# io-board-b-b.net
KiCad netlist of a schematic drawn in EAGLE
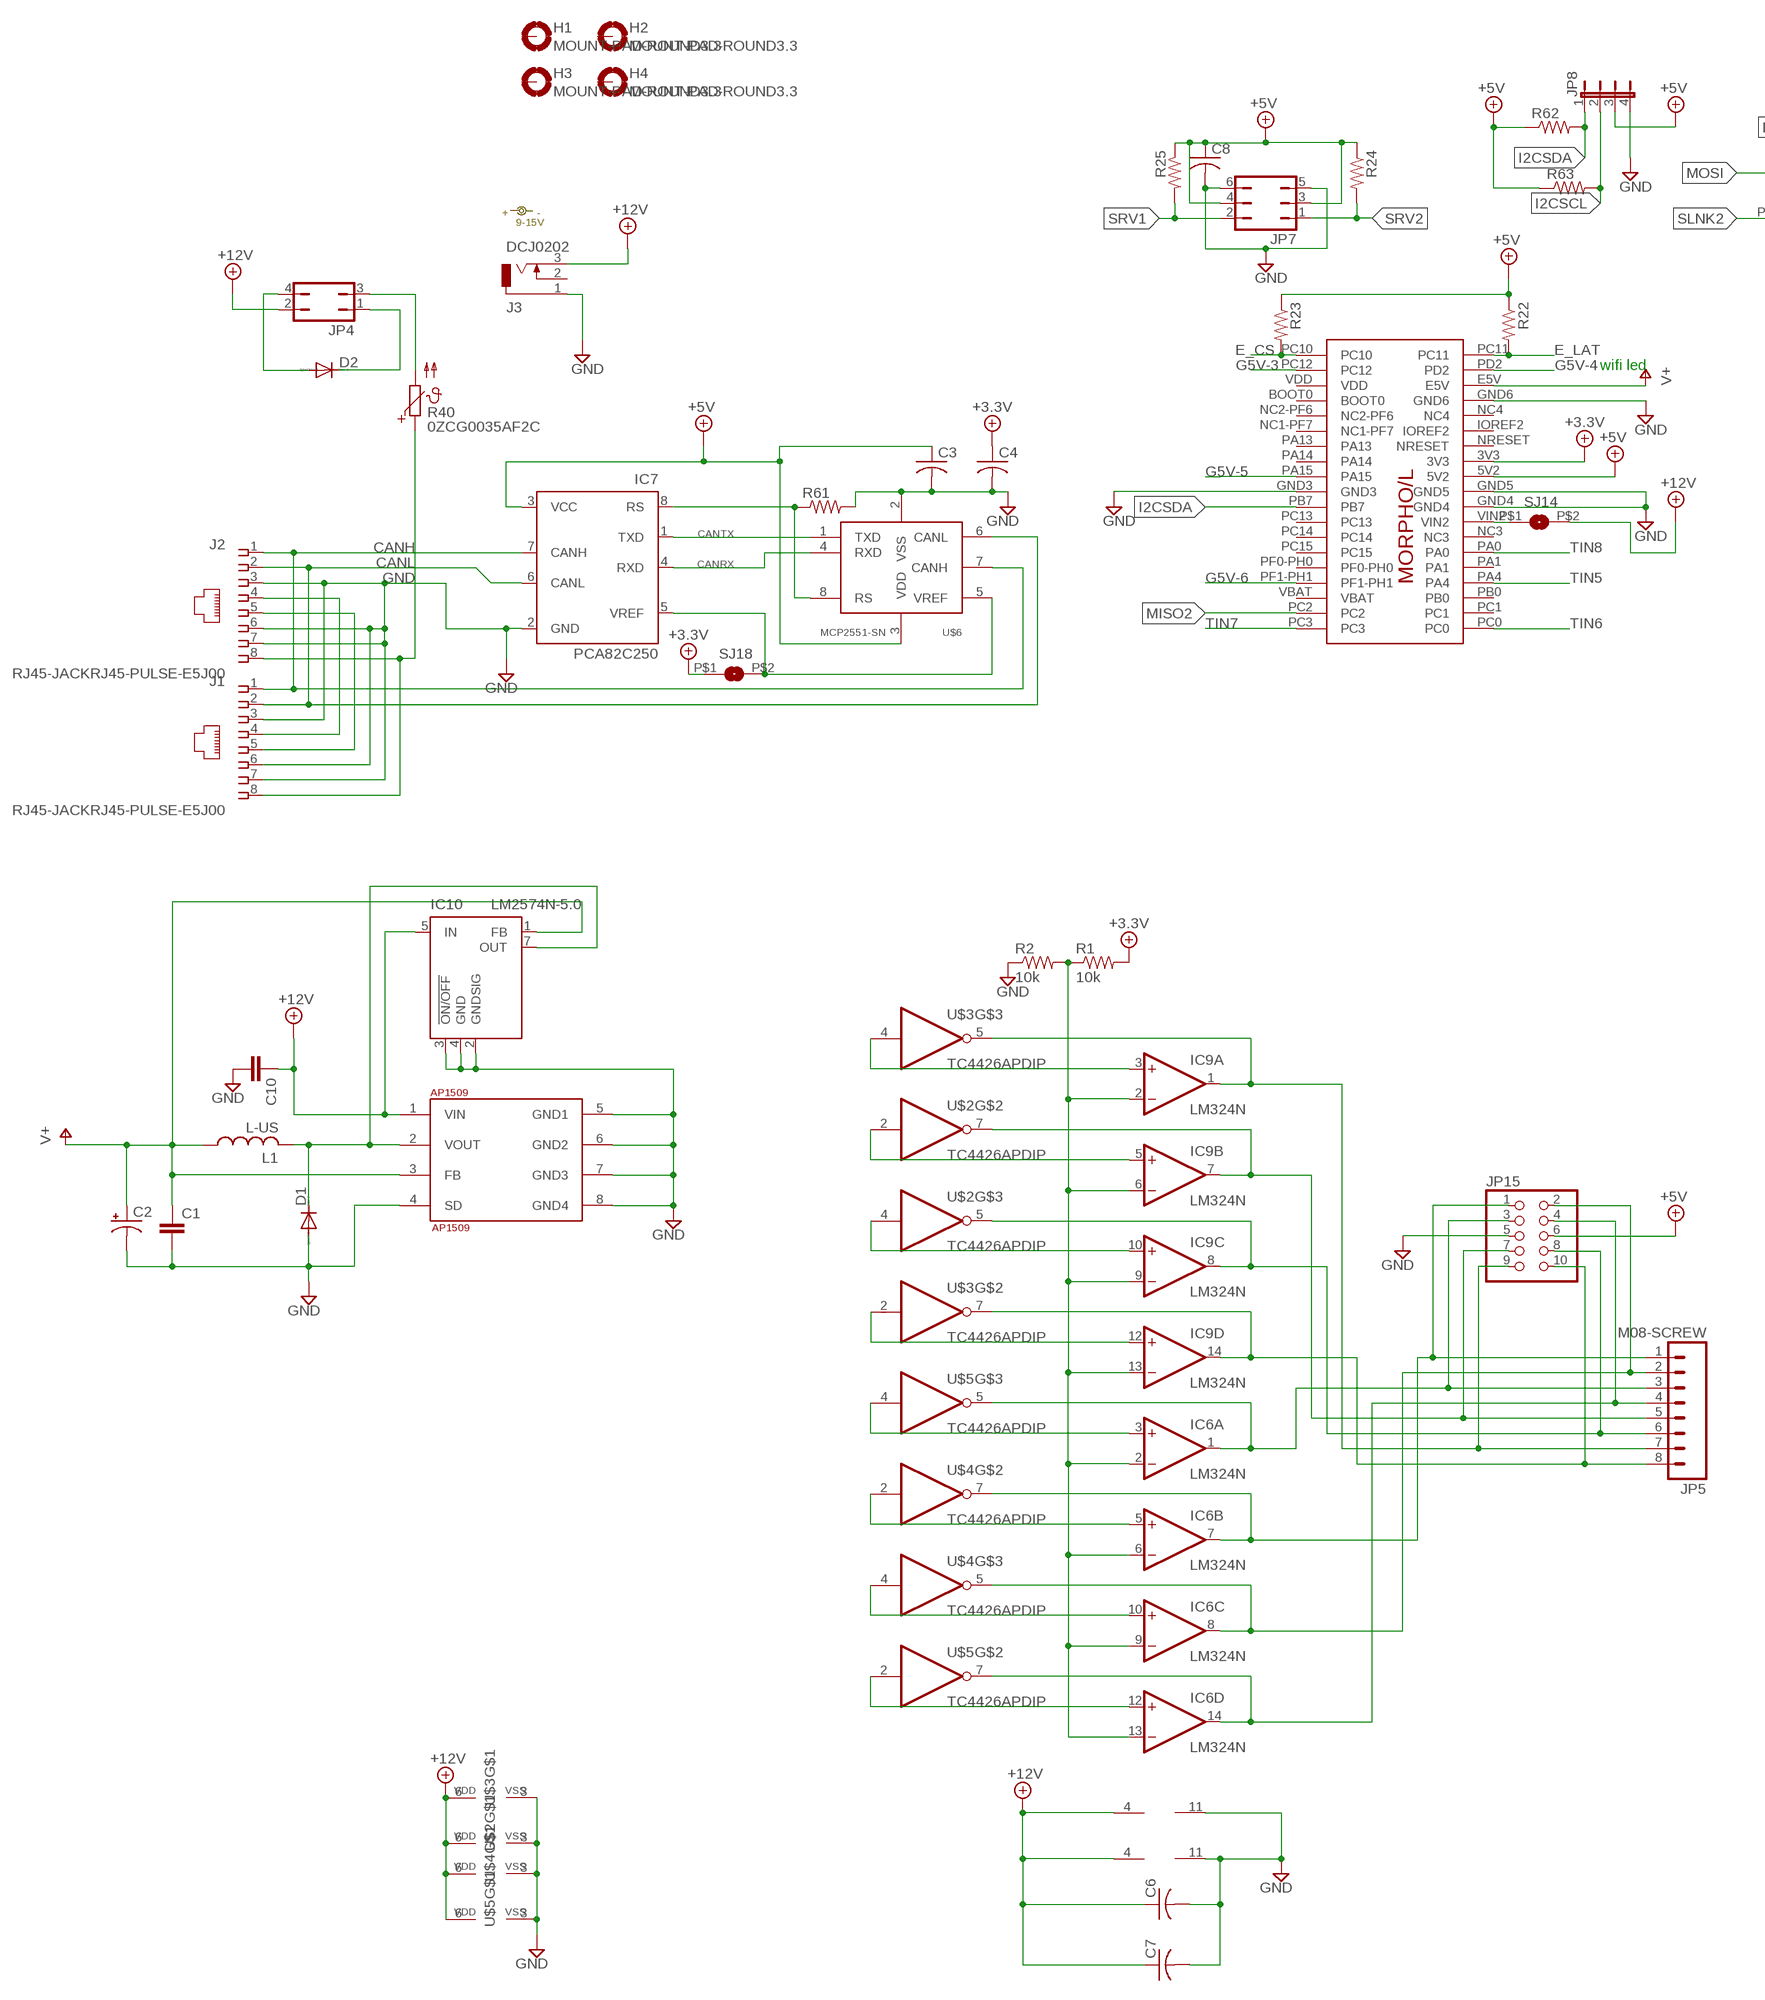
[diagram p0: schematic, sheet 1, part 1 of 2]
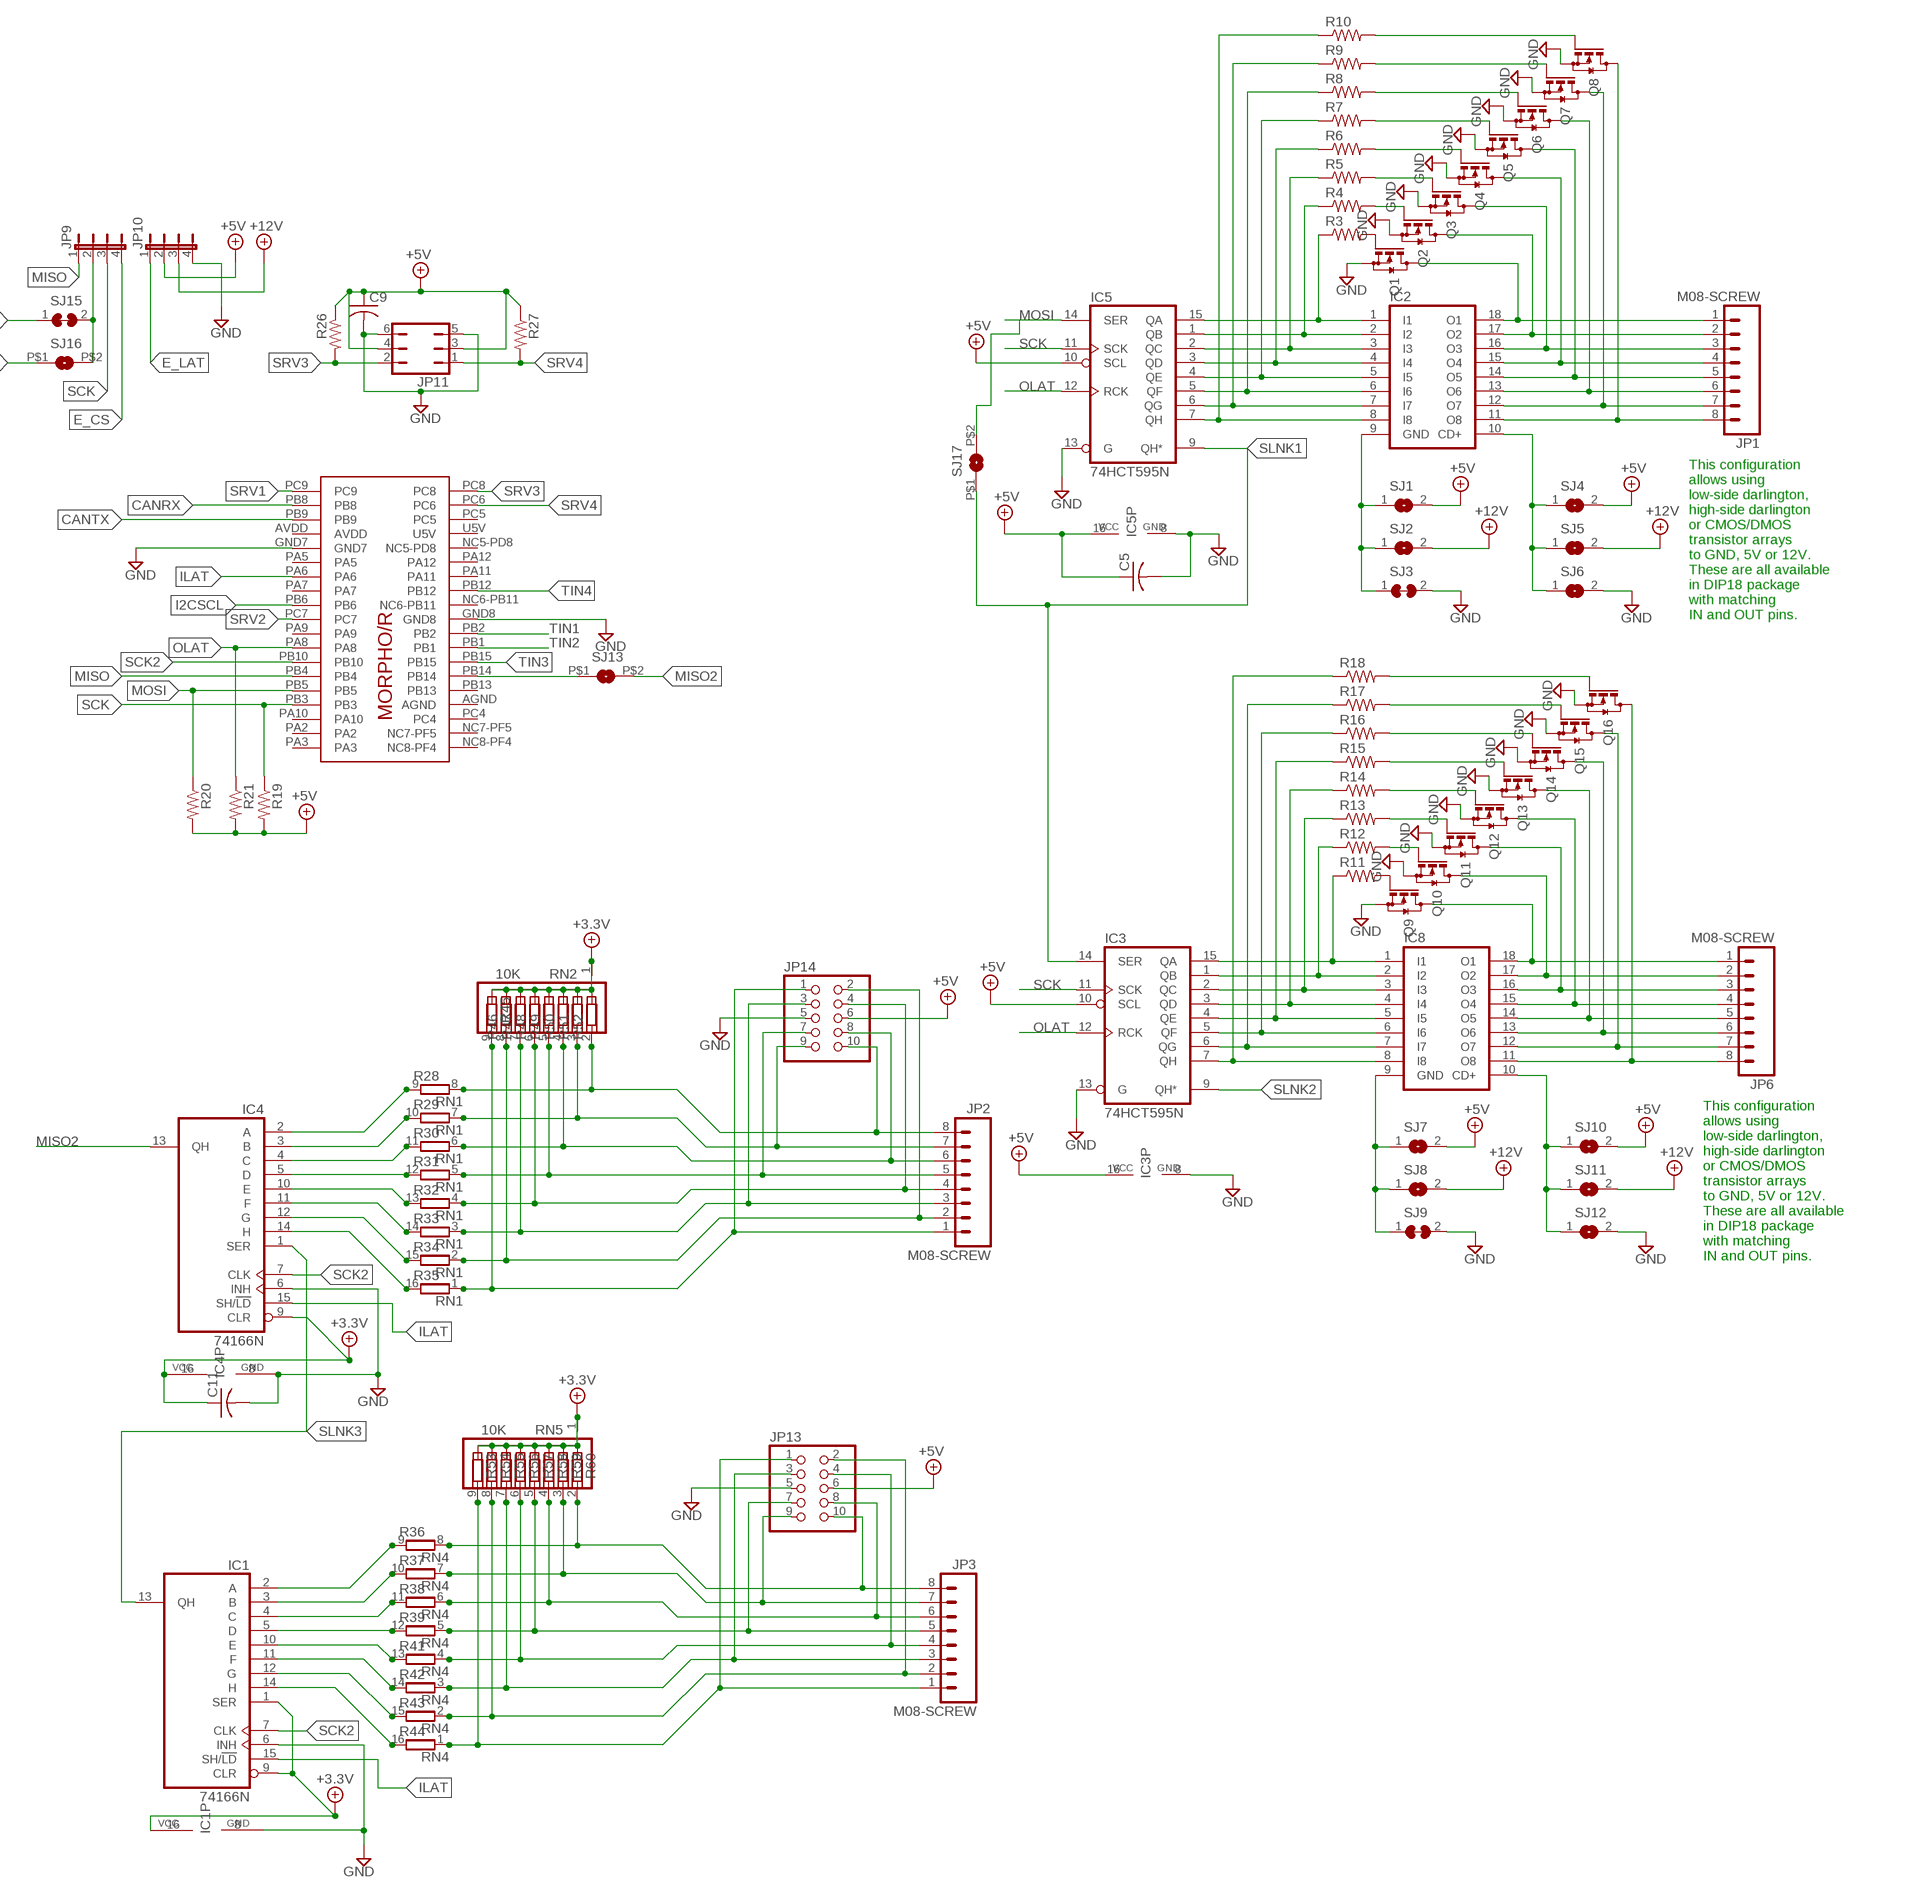
[diagram p1: schematic, sheet 1, part 2 of 2]

(export (version "E")
  (design (tool "Eeschema 10.0.6"))
  (components
    (comp (ref "+12V")
      (value "9-15V")
      (footprint "eagle-import:POWER_USAGE")
      (libsource (lib "eagle-import") (part "DOC-POWER_LABEL"))
    )
    (comp (ref "AP1509")
      (value "AP1509")
      (footprint "eagle-import:SO-08")
      (libsource (lib "eagle-import") (part "AP1509"))
    )
    (comp (ref "C1")
      (value "C-EUC1206")
      (footprint "eagle-import:C1206")
      (libsource (lib "eagle-import") (part "C-EUC1206"))
    )
    (comp (ref "C2")
      (value "CPOL-USE2.5-5")
      (footprint "eagle-import:E2,5-5")
      (libsource (lib "eagle-import") (part "CPOL-USE2.5-5"))
    )
    (comp (ref "C3")
      (value "C-USC0805")
      (footprint "eagle-import:C0805")
      (libsource (lib "eagle-import") (part "C-USC0805"))
    )
    (comp (ref "C4")
      (value "C-USC0805")
      (footprint "eagle-import:C0805")
      (libsource (lib "eagle-import") (part "C-USC0805"))
    )
    (comp (ref "C5")
      (value "C-USC0805")
      (footprint "eagle-import:C0805")
      (libsource (lib "eagle-import") (part "C-USC0805"))
    )
    (comp (ref "C6")
      (value "C-USC1206")
      (footprint "eagle-import:C1206")
      (libsource (lib "eagle-import") (part "C-USC1206"))
    )
    (comp (ref "C7")
      (value "C-USC1206")
      (footprint "eagle-import:C1206")
      (libsource (lib "eagle-import") (part "C-USC1206"))
    )
    (comp (ref "C8")
      (value "C-USC1206")
      (footprint "eagle-import:C1206")
      (libsource (lib "eagle-import") (part "C-USC1206"))
    )
    (comp (ref "C9")
      (value "C-USC1206")
      (footprint "eagle-import:C1206")
      (libsource (lib "eagle-import") (part "C-USC1206"))
    )
    (comp (ref "C10")
      (value "C-EUC1206")
      (footprint "eagle-import:C1206")
      (libsource (lib "eagle-import") (part "C-EUC1206"))
    )
    (comp (ref "C11")
      (value "C-USC0805")
      (footprint "eagle-import:C0805")
      (libsource (lib "eagle-import") (part "C-USC0805"))
    )
    (comp (ref "D1")
      (value "DIODE-DO41-7.6")
      (footprint "eagle-import:DO41-7.6")
      (libsource (lib "eagle-import") (part "DIODE-DO41-7.6"))
    )
    (comp (ref "D2")
      (value "DIODE-DO41-7.6")
      (footprint "eagle-import:DO41-7.6")
      (libsource (lib "eagle-import") (part "DIODE-DO41-7.6"))
    )
    (comp (ref "H1")
      (value "MOUNT-PAD-ROUND3.3")
      (footprint "eagle-import:3,3-PAD")
      (libsource (lib "eagle-import") (part "MOUNT-PAD-ROUND3.3"))
    )
    (comp (ref "H2")
      (value "MOUNT-PAD-ROUND3.3")
      (footprint "eagle-import:3,3-PAD")
      (libsource (lib "eagle-import") (part "MOUNT-PAD-ROUND3.3"))
    )
    (comp (ref "H3")
      (value "MOUNT-PAD-ROUND3.3")
      (footprint "eagle-import:3,3-PAD")
      (libsource (lib "eagle-import") (part "MOUNT-PAD-ROUND3.3"))
    )
    (comp (ref "H4")
      (value "MOUNT-PAD-ROUND3.3")
      (footprint "eagle-import:3,3-PAD")
      (libsource (lib "eagle-import") (part "MOUNT-PAD-ROUND3.3"))
    )
    (comp (ref "IC1")
      (value "74166N")
      (footprint "eagle-import:DIL16")
      (libsource (lib "eagle-import") (part "74166N"))
    )
    (comp (ref "IC2")
      (value "ULN2803A")
      (footprint "eagle-import:DIL18-THIN")
      (libsource (lib "eagle-import") (part "ULN2803A"))
    )
    (comp (ref "IC3")
      (value "74HCT595N")
      (footprint "eagle-import:DIL16")
      (libsource (lib "eagle-import") (part "74595NHCT"))
    )
    (comp (ref "IC4")
      (value "74166N")
      (footprint "eagle-import:DIL16")
      (libsource (lib "eagle-import") (part "74166N"))
    )
    (comp (ref "IC5")
      (value "74HCT595N")
      (footprint "eagle-import:DIL16")
      (libsource (lib "eagle-import") (part "74595NHCT"))
    )
    (comp (ref "IC6")
      (value "LM324N")
      (footprint "eagle-import:DIL14")
      (libsource (lib "eagle-import") (part "LM324N"))
    )
    (comp (ref "IC7")
      (value "PCA82C250")
      (footprint "eagle-import:DIL08")
      (libsource (lib "eagle-import") (part "PCA82C250"))
    )
    (comp (ref "IC8")
      (value "ULN2803A")
      (footprint "eagle-import:DIL18-THIN")
      (libsource (lib "eagle-import") (part "ULN2803A"))
    )
    (comp (ref "IC9")
      (value "LM324N")
      (footprint "eagle-import:DIL14")
      (libsource (lib "eagle-import") (part "LM324N"))
    )
    (comp (ref "IC10")
      (value "LM2574N-5.0")
      (footprint "eagle-import:DIL08")
      (libsource (lib "eagle-import") (part "LM2574?-N5.0"))
    )
    (comp (ref "J1")
      (value "RJ45-JACKRJ45-PULSE-E5J00")
      (footprint "eagle-import:RJ45-PULSE-E5J88")
      (libsource (lib "eagle-import") (part "RJ45-JACKRJ45-PULSE-E5J00"))
    )
    (comp (ref "J2")
      (value "RJ45-JACKRJ45-PULSE-E5J00")
      (footprint "eagle-import:RJ45-PULSE-E5J88")
      (libsource (lib "eagle-import") (part "RJ45-JACKRJ45-PULSE-E5J00"))
    )
    (comp (ref "J3")
      (value "DCJ0202")
      (footprint "eagle-import:DCJ0202")
      (libsource (lib "eagle-import") (part "DCJ0202"))
    )
    (comp (ref "JP1")
      (value "M08-SCREW")
      (footprint "eagle-import:1X08_TERMINAL")
      (libsource (lib "eagle-import") (part "M08-SCREW"))
    )
    (comp (ref "JP2")
      (value "M08-SCREW")
      (footprint "eagle-import:1X08_TERMINAL")
      (libsource (lib "eagle-import") (part "M08-SCREW"))
    )
    (comp (ref "JP3")
      (value "M08-SCREW")
      (footprint "eagle-import:1X08_TERMINAL")
      (libsource (lib "eagle-import") (part "M08-SCREW"))
    )
    (comp (ref "JP4")
      (value "JP2Q")
      (footprint "eagle-import:JP2Q")
      (libsource (lib "eagle-import") (part "JP2Q"))
    )
    (comp (ref "JP5")
      (value "M08-SCREW")
      (footprint "eagle-import:1X08_TERMINAL")
      (libsource (lib "eagle-import") (part "M08-SCREW"))
    )
    (comp (ref "JP6")
      (value "M08-SCREW")
      (footprint "eagle-import:1X08_TERMINAL")
      (libsource (lib "eagle-import") (part "M08-SCREW"))
    )
    (comp (ref "JP7")
      (value "JP3Q")
      (footprint "eagle-import:JP3Q")
      (libsource (lib "eagle-import") (part "JP3Q"))
    )
    (comp (ref "JP8")
      (value "JP4-FLAT")
      (footprint "eagle-import:JP4F")
      (libsource (lib "eagle-import") (part "JP4-FLAT"))
    )
    (comp (ref "JP9")
      (value "JP4-FLAT")
      (footprint "eagle-import:JP4F")
      (libsource (lib "eagle-import") (part "JP4-FLAT"))
    )
    (comp (ref "JP10")
      (value "JP4-FLAT")
      (footprint "eagle-import:JP4F")
      (libsource (lib "eagle-import") (part "JP4-FLAT"))
    )
    (comp (ref "JP11")
      (value "JP3Q")
      (footprint "eagle-import:JP3Q")
      (libsource (lib "eagle-import") (part "JP3Q"))
    )
    (comp (ref "JP13")
      (value "PINHD-2X5CN")
      (footprint "eagle-import:CON10M")
      (libsource (lib "eagle-import") (part "PINHD-2X5CN"))
    )
    (comp (ref "JP14")
      (value "PINHD-2X5CN")
      (footprint "eagle-import:CON10M")
      (libsource (lib "eagle-import") (part "PINHD-2X5CN"))
    )
    (comp (ref "JP15")
      (value "PINHD-2X5CN")
      (footprint "eagle-import:CON10M")
      (libsource (lib "eagle-import") (part "PINHD-2X5CN"))
    )
    (comp (ref "L1")
      (value "L-US")
      (footprint "eagle-import:L5-8,5")
      (libsource (lib "eagle-import") (part "L-US"))
    )
    (comp (ref "Q1")
      (value "BSS123")
      (footprint "eagle-import:SOT23")
      (libsource (lib "eagle-import") (part "BSS123"))
    )
    (comp (ref "Q2")
      (value "BSS123")
      (footprint "eagle-import:SOT23")
      (libsource (lib "eagle-import") (part "BSS123"))
    )
    (comp (ref "Q3")
      (value "BSS123")
      (footprint "eagle-import:SOT23")
      (libsource (lib "eagle-import") (part "BSS123"))
    )
    (comp (ref "Q4")
      (value "BSS123")
      (footprint "eagle-import:SOT23")
      (libsource (lib "eagle-import") (part "BSS123"))
    )
    (comp (ref "Q5")
      (value "BSS123")
      (footprint "eagle-import:SOT23")
      (libsource (lib "eagle-import") (part "BSS123"))
    )
    (comp (ref "Q6")
      (value "BSS123")
      (footprint "eagle-import:SOT23")
      (libsource (lib "eagle-import") (part "BSS123"))
    )
    (comp (ref "Q7")
      (value "BSS123")
      (footprint "eagle-import:SOT23")
      (libsource (lib "eagle-import") (part "BSS123"))
    )
    (comp (ref "Q8")
      (value "BSS123")
      (footprint "eagle-import:SOT23")
      (libsource (lib "eagle-import") (part "BSS123"))
    )
    (comp (ref "Q9")
      (value "BSS123")
      (footprint "eagle-import:SOT23")
      (libsource (lib "eagle-import") (part "BSS123"))
    )
    (comp (ref "Q10")
      (value "BSS123")
      (footprint "eagle-import:SOT23")
      (libsource (lib "eagle-import") (part "BSS123"))
    )
    (comp (ref "Q11")
      (value "BSS123")
      (footprint "eagle-import:SOT23")
      (libsource (lib "eagle-import") (part "BSS123"))
    )
    (comp (ref "Q12")
      (value "BSS123")
      (footprint "eagle-import:SOT23")
      (libsource (lib "eagle-import") (part "BSS123"))
    )
    (comp (ref "Q13")
      (value "BSS123")
      (footprint "eagle-import:SOT23")
      (libsource (lib "eagle-import") (part "BSS123"))
    )
    (comp (ref "Q14")
      (value "BSS123")
      (footprint "eagle-import:SOT23")
      (libsource (lib "eagle-import") (part "BSS123"))
    )
    (comp (ref "Q15")
      (value "BSS123")
      (footprint "eagle-import:SOT23")
      (libsource (lib "eagle-import") (part "BSS123"))
    )
    (comp (ref "Q16")
      (value "BSS123")
      (footprint "eagle-import:SOT23")
      (libsource (lib "eagle-import") (part "BSS123"))
    )
    (comp (ref "R1")
      (value "10k")
      (footprint "eagle-import:R0805")
      (libsource (lib "eagle-import") (part "R-US_R0805"))
    )
    (comp (ref "R2")
      (value "10k")
      (footprint "eagle-import:R0805")
      (libsource (lib "eagle-import") (part "R-US_R0805"))
    )
    (comp (ref "R3")
      (value "R-US_R0603")
      (footprint "eagle-import:R0603")
      (libsource (lib "eagle-import") (part "R-US_R0603"))
    )
    (comp (ref "R4")
      (value "R-US_R0603")
      (footprint "eagle-import:R0603")
      (libsource (lib "eagle-import") (part "R-US_R0603"))
    )
    (comp (ref "R5")
      (value "R-US_R0603")
      (footprint "eagle-import:R0603")
      (libsource (lib "eagle-import") (part "R-US_R0603"))
    )
    (comp (ref "R6")
      (value "R-US_R0603")
      (footprint "eagle-import:R0603")
      (libsource (lib "eagle-import") (part "R-US_R0603"))
    )
    (comp (ref "R7")
      (value "R-US_R0603")
      (footprint "eagle-import:R0603")
      (libsource (lib "eagle-import") (part "R-US_R0603"))
    )
    (comp (ref "R8")
      (value "R-US_R0603")
      (footprint "eagle-import:R0603")
      (libsource (lib "eagle-import") (part "R-US_R0603"))
    )
    (comp (ref "R9")
      (value "R-US_R0603")
      (footprint "eagle-import:R0603")
      (libsource (lib "eagle-import") (part "R-US_R0603"))
    )
    (comp (ref "R10")
      (value "R-US_R0603")
      (footprint "eagle-import:R0603")
      (libsource (lib "eagle-import") (part "R-US_R0603"))
    )
    (comp (ref "R11")
      (value "R-US_R0603")
      (footprint "eagle-import:R0603")
      (libsource (lib "eagle-import") (part "R-US_R0603"))
    )
    (comp (ref "R12")
      (value "R-US_R0603")
      (footprint "eagle-import:R0603")
      (libsource (lib "eagle-import") (part "R-US_R0603"))
    )
    (comp (ref "R13")
      (value "R-US_R0603")
      (footprint "eagle-import:R0603")
      (libsource (lib "eagle-import") (part "R-US_R0603"))
    )
    (comp (ref "R14")
      (value "R-US_R0603")
      (footprint "eagle-import:R0603")
      (libsource (lib "eagle-import") (part "R-US_R0603"))
    )
    (comp (ref "R15")
      (value "R-US_R0603")
      (footprint "eagle-import:R0603")
      (libsource (lib "eagle-import") (part "R-US_R0603"))
    )
    (comp (ref "R16")
      (value "R-US_R0603")
      (footprint "eagle-import:R0603")
      (libsource (lib "eagle-import") (part "R-US_R0603"))
    )
    (comp (ref "R17")
      (value "R-US_R0603")
      (footprint "eagle-import:R0603")
      (libsource (lib "eagle-import") (part "R-US_R0603"))
    )
    (comp (ref "R18")
      (value "R-US_R0603")
      (footprint "eagle-import:R0603")
      (libsource (lib "eagle-import") (part "R-US_R0603"))
    )
    (comp (ref "R19")
      (value "R-US_R0805")
      (footprint "eagle-import:R0805")
      (libsource (lib "eagle-import") (part "rcl_334_R-US_R0805"))
    )
    (comp (ref "R20")
      (value "R-US_R0805")
      (footprint "eagle-import:R0805")
      (libsource (lib "eagle-import") (part "rcl_334_R-US_R0805"))
    )
    (comp (ref "R21")
      (value "R-US_R0805")
      (footprint "eagle-import:R0805")
      (libsource (lib "eagle-import") (part "rcl_334_R-US_R0805"))
    )
    (comp (ref "R22")
      (value "R-US_R0805")
      (footprint "eagle-import:R0805")
      (libsource (lib "eagle-import") (part "rcl_334_R-US_R0805"))
    )
    (comp (ref "R23")
      (value "R-US_R0805")
      (footprint "eagle-import:R0805")
      (libsource (lib "eagle-import") (part "rcl_334_R-US_R0805"))
    )
    (comp (ref "R24")
      (value "R-US_R0805")
      (footprint "eagle-import:R0805")
      (libsource (lib "eagle-import") (part "rcl_334_R-US_R0805"))
    )
    (comp (ref "R25")
      (value "R-US_R0805")
      (footprint "eagle-import:R0805")
      (libsource (lib "eagle-import") (part "rcl_334_R-US_R0805"))
    )
    (comp (ref "R26")
      (value "R-US_R0805")
      (footprint "eagle-import:R0805")
      (libsource (lib "eagle-import") (part "rcl_334_R-US_R0805"))
    )
    (comp (ref "R27")
      (value "R-US_R0805")
      (footprint "eagle-import:R0805")
      (libsource (lib "eagle-import") (part "rcl_334_R-US_R0805"))
    )
    (comp (ref "R28")
      (value "R-EU_R0603")
      (footprint "eagle-import:R0603")
      (libsource (lib "eagle-import") (part "R-EU_R0603"))
    )
    (comp (ref "R29")
      (value "R-EU_R0603")
      (footprint "eagle-import:R0603")
      (libsource (lib "eagle-import") (part "R-EU_R0603"))
    )
    (comp (ref "R30")
      (value "R-EU_R0603")
      (footprint "eagle-import:R0603")
      (libsource (lib "eagle-import") (part "R-EU_R0603"))
    )
    (comp (ref "R31")
      (value "R-EU_R0603")
      (footprint "eagle-import:R0603")
      (libsource (lib "eagle-import") (part "R-EU_R0603"))
    )
    (comp (ref "R32")
      (value "R-EU_R0603")
      (footprint "eagle-import:R0603")
      (libsource (lib "eagle-import") (part "R-EU_R0603"))
    )
    (comp (ref "R33")
      (value "R-EU_R0603")
      (footprint "eagle-import:R0603")
      (libsource (lib "eagle-import") (part "R-EU_R0603"))
    )
    (comp (ref "R34")
      (value "R-EU_R0603")
      (footprint "eagle-import:R0603")
      (libsource (lib "eagle-import") (part "R-EU_R0603"))
    )
    (comp (ref "R35")
      (value "R-EU_R0603")
      (footprint "eagle-import:R0603")
      (libsource (lib "eagle-import") (part "R-EU_R0603"))
    )
    (comp (ref "R36")
      (value "R-EU_R0603")
      (footprint "eagle-import:R0603")
      (libsource (lib "eagle-import") (part "R-EU_R0603"))
    )
    (comp (ref "R37")
      (value "R-EU_R0603")
      (footprint "eagle-import:R0603")
      (libsource (lib "eagle-import") (part "R-EU_R0603"))
    )
    (comp (ref "R38")
      (value "R-EU_R0603")
      (footprint "eagle-import:R0603")
      (libsource (lib "eagle-import") (part "R-EU_R0603"))
    )
    (comp (ref "R39")
      (value "R-EU_R0603")
      (footprint "eagle-import:R0603")
      (libsource (lib "eagle-import") (part "R-EU_R0603"))
    )
    (comp (ref "R40")
      (value "0ZCG0035AF2C")
      (footprint "eagle-import:PTC1812")
      (libsource (lib "eagle-import") (part "PTC_1812"))
    )
    (comp (ref "R41")
      (value "R-EU_R0603")
      (footprint "eagle-import:R0603")
      (libsource (lib "eagle-import") (part "R-EU_R0603"))
    )
    (comp (ref "R42")
      (value "R-EU_R0603")
      (footprint "eagle-import:R0603")
      (libsource (lib "eagle-import") (part "R-EU_R0603"))
    )
    (comp (ref "R43")
      (value "R-EU_R0603")
      (footprint "eagle-import:R0603")
      (libsource (lib "eagle-import") (part "R-EU_R0603"))
    )
    (comp (ref "R44")
      (value "R-EU_R0603")
      (footprint "eagle-import:R0603")
      (libsource (lib "eagle-import") (part "R-EU_R0603"))
    )
    (comp (ref "R45")
      (value "R-EU_R0603")
      (footprint "eagle-import:R0603")
      (libsource (lib "eagle-import") (part "R-EU_R0603"))
    )
    (comp (ref "R46")
      (value "R-EU_R0603")
      (footprint "eagle-import:R0603")
      (libsource (lib "eagle-import") (part "R-EU_R0603"))
    )
    (comp (ref "R47")
      (value "R-EU_R0603")
      (footprint "eagle-import:R0603")
      (libsource (lib "eagle-import") (part "R-EU_R0603"))
    )
    (comp (ref "R48")
      (value "R-EU_R0603")
      (footprint "eagle-import:R0603")
      (libsource (lib "eagle-import") (part "R-EU_R0603"))
    )
    (comp (ref "R49")
      (value "R-EU_R0603")
      (footprint "eagle-import:R0603")
      (libsource (lib "eagle-import") (part "R-EU_R0603"))
    )
    (comp (ref "R50")
      (value "R-EU_R0603")
      (footprint "eagle-import:R0603")
      (libsource (lib "eagle-import") (part "R-EU_R0603"))
    )
    (comp (ref "R51")
      (value "R-EU_R0603")
      (footprint "eagle-import:R0603")
      (libsource (lib "eagle-import") (part "R-EU_R0603"))
    )
    (comp (ref "R52")
      (value "R-EU_R0603")
      (footprint "eagle-import:R0603")
      (libsource (lib "eagle-import") (part "R-EU_R0603"))
    )
    (comp (ref "R53")
      (value "R-EU_R0603")
      (footprint "eagle-import:R0603")
      (libsource (lib "eagle-import") (part "R-EU_R0603"))
    )
    (comp (ref "R54")
      (value "R-EU_R0603")
      (footprint "eagle-import:R0603")
      (libsource (lib "eagle-import") (part "R-EU_R0603"))
    )
    (comp (ref "R55")
      (value "R-EU_R0603")
      (footprint "eagle-import:R0603")
      (libsource (lib "eagle-import") (part "R-EU_R0603"))
    )
    (comp (ref "R56")
      (value "R-EU_R0603")
      (footprint "eagle-import:R0603")
      (libsource (lib "eagle-import") (part "R-EU_R0603"))
    )
    (comp (ref "R57")
      (value "R-EU_R0603")
      (footprint "eagle-import:R0603")
      (libsource (lib "eagle-import") (part "R-EU_R0603"))
    )
    (comp (ref "R58")
      (value "R-EU_R0603")
      (footprint "eagle-import:R0603")
      (libsource (lib "eagle-import") (part "R-EU_R0603"))
    )
    (comp (ref "R59")
      (value "R-EU_R0603")
      (footprint "eagle-import:R0603")
      (libsource (lib "eagle-import") (part "R-EU_R0603"))
    )
    (comp (ref "R60")
      (value "R-EU_R0603")
      (footprint "eagle-import:R0603")
      (libsource (lib "eagle-import") (part "R-EU_R0603"))
    )
    (comp (ref "R61")
      (value "R-US_R0805")
      (footprint "eagle-import:R0805")
      (libsource (lib "eagle-import") (part "rcl_334_R-US_R0805"))
    )
    (comp (ref "R62")
      (value "R-US_R0805")
      (footprint "eagle-import:R0805")
      (libsource (lib "eagle-import") (part "rcl_334_R-US_R0805"))
    )
    (comp (ref "R63")
      (value "R-US_R0805")
      (footprint "eagle-import:R0805")
      (libsource (lib "eagle-import") (part "rcl_334_R-US_R0805"))
    )
    (comp (ref "RN1")
      (value "8R-P")
      (footprint "eagle-import:DIL16")
      (libsource (lib "eagle-import") (part "8R-P"))
    )
    (comp (ref "RN2")
      (value "10K")
      (footprint "eagle-import:SIL9")
      (libsource (lib "eagle-import") (part "G08R"))
    )
    (comp (ref "RN4")
      (value "8R-P")
      (footprint "eagle-import:DIL16")
      (libsource (lib "eagle-import") (part "8R-P"))
    )
    (comp (ref "RN5")
      (value "10K")
      (footprint "eagle-import:SIL9")
      (libsource (lib "eagle-import") (part "G08R"))
    )
    (comp (ref "SJ1")
      (value "SJ")
      (footprint "eagle-import:SJ-RND")
      (libsource (lib "eagle-import") (part "SJ"))
    )
    (comp (ref "SJ2")
      (value "SJ")
      (footprint "eagle-import:SJ-RND")
      (libsource (lib "eagle-import") (part "SJ"))
    )
    (comp (ref "SJ3")
      (value "SJ-C")
      (footprint "eagle-import:SJW-C")
      (libsource (lib "eagle-import") (part "SJ-C"))
    )
    (comp (ref "SJ4")
      (value "SJ")
      (footprint "eagle-import:SJ-RND")
      (libsource (lib "eagle-import") (part "SJ"))
    )
    (comp (ref "SJ5")
      (value "SJ")
      (footprint "eagle-import:SJ-RND")
      (libsource (lib "eagle-import") (part "SJ"))
    )
    (comp (ref "SJ6")
      (value "SJ")
      (footprint "eagle-import:SJ-RND")
      (libsource (lib "eagle-import") (part "SJ"))
    )
    (comp (ref "SJ7")
      (value "SJ")
      (footprint "eagle-import:SJ-RND")
      (libsource (lib "eagle-import") (part "SJ"))
    )
    (comp (ref "SJ8")
      (value "SJ")
      (footprint "eagle-import:SJ-RND")
      (libsource (lib "eagle-import") (part "SJ"))
    )
    (comp (ref "SJ9")
      (value "SJ-C")
      (footprint "eagle-import:SJW-C")
      (libsource (lib "eagle-import") (part "SJ-C"))
    )
    (comp (ref "SJ10")
      (value "SJ")
      (footprint "eagle-import:SJ-RND")
      (libsource (lib "eagle-import") (part "SJ"))
    )
    (comp (ref "SJ11")
      (value "SJ")
      (footprint "eagle-import:SJ-RND")
      (libsource (lib "eagle-import") (part "SJ"))
    )
    (comp (ref "SJ12")
      (value "SJ")
      (footprint "eagle-import:SJ-RND")
      (libsource (lib "eagle-import") (part "SJ"))
    )
    (comp (ref "SJ13")
      (value "SJRND2")
      (footprint "eagle-import:SJ_RND2")
      (libsource (lib "eagle-import") (part "SJRND2"))
    )
    (comp (ref "SJ14")
      (value "SJRND2")
      (footprint "eagle-import:SJ_RND2")
      (libsource (lib "eagle-import") (part "SJRND2"))
    )
    (comp (ref "SJ15")
      (value "SJ-C")
      (footprint "eagle-import:SJW-C")
      (libsource (lib "eagle-import") (part "SJ-C"))
    )
    (comp (ref "SJ16")
      (value "SJRND2")
      (footprint "eagle-import:SJ_RND2")
      (libsource (lib "eagle-import") (part "SJRND2"))
    )
    (comp (ref "SJ17")
      (value "SJRND2")
      (footprint "eagle-import:SJ_RND2")
      (libsource (lib "eagle-import") (part "SJRND2"))
    )
    (comp (ref "SJ18")
      (value "SJRND2")
      (footprint "eagle-import:SJ_RND2")
      (libsource (lib "eagle-import") (part "SJRND2"))
    )
    (comp (ref "U$1")
      (value "NUCLEO_64_GENERIC")
      (footprint "eagle-import:NUCLEO_BRD_BASE64")
      (libsource (lib "eagle-import") (part "NUCLEO_64_GENERIC"))
    )
    (comp (ref "U$2")
      (value "TC4426APDIP")
      (footprint "eagle-import:DIL08-LONG")
      (libsource (lib "eagle-import") (part "TC4426APDIP"))
    )
    (comp (ref "U$3")
      (value "TC4426APDIP")
      (footprint "eagle-import:DIL08-LONG")
      (libsource (lib "eagle-import") (part "TC4426APDIP"))
    )
    (comp (ref "U$4")
      (value "TC4426APDIP")
      (footprint "eagle-import:DIL08-LONG")
      (libsource (lib "eagle-import") (part "TC4426APDIP"))
    )
    (comp (ref "U$5")
      (value "TC4426APDIP")
      (footprint "eagle-import:DIL08-LONG")
      (libsource (lib "eagle-import") (part "TC4426APDIP"))
    )
    (comp (ref "U$6")
      (value "MCP2551-SN")
      (footprint "eagle-import:SO-08")
      (libsource (lib "eagle-import") (part "MCP2551-SN"))
    )
  )
  (nets
    (net (code "1") (name "+3.3V") (class "Default")
      (node (ref "C11") (pin "1") (pinfunction "1_1") (pintype "passive"))
      (node (ref "C4") (pin "1") (pinfunction "1_1") (pintype "passive"))
      (node (ref "IC1") (pin "1") (pinfunction "SER_1") (pintype "input"))
      (node (ref "IC1") (pin "16") (pinfunction "VCC_16") (pintype "power_in"))
      (node (ref "IC1") (pin "9") (pinfunction "CLR_9") (pintype "input"))
      (node (ref "IC4") (pin "16") (pinfunction "VCC_16") (pintype "power_in"))
      (node (ref "IC4") (pin "9") (pinfunction "CLR_9") (pintype "input"))
      (node (ref "R1") (pin "2") (pinfunction "2_2") (pintype "passive"))
      (node (ref "R45") (pin "1") (pinfunction "1_1") (pintype "passive"))
      (node (ref "R46") (pin "2") (pinfunction "2_2") (pintype "passive"))
      (node (ref "R47") (pin "2") (pinfunction "2_2") (pintype "passive"))
      (node (ref "R48") (pin "2") (pinfunction "2_2") (pintype "passive"))
      (node (ref "R49") (pin "2") (pinfunction "2_2") (pintype "passive"))
      (node (ref "R50") (pin "2") (pinfunction "2_2") (pintype "passive"))
      (node (ref "R51") (pin "2") (pinfunction "2_2") (pintype "passive"))
      (node (ref "R52") (pin "2") (pinfunction "2_2") (pintype "passive"))
      (node (ref "R53") (pin "1") (pinfunction "1_1") (pintype "passive"))
      (node (ref "R54") (pin "1") (pinfunction "1_1") (pintype "passive"))
      (node (ref "R55") (pin "1") (pinfunction "1_1") (pintype "passive"))
      (node (ref "R56") (pin "1") (pinfunction "1_1") (pintype "passive"))
      (node (ref "R57") (pin "1") (pinfunction "1_1") (pintype "passive"))
      (node (ref "R58") (pin "1") (pinfunction "1_1") (pintype "passive"))
      (node (ref "R59") (pin "1") (pinfunction "1_1") (pintype "passive"))
      (node (ref "R60") (pin "1") (pinfunction "1_1") (pintype "passive"))
      (node (ref "RN2") (pin "1") (pinfunction "1_1") (pintype "passive"))
      (node (ref "RN5") (pin "1") (pinfunction "1_1") (pintype "passive"))
      (node (ref "SJ18") (pin "P$1") (pinfunction "1_P$1") (pintype "passive"))
      (node (ref "U$1") (pin "3V3") (pinfunction "3V3_3V3") (pintype "power_in"))
    )
    (net (code "2") (name "+5V") (class "Default")
      (node (ref "C3") (pin "1") (pinfunction "1_1") (pintype "passive"))
      (node (ref "C5") (pin "1") (pinfunction "1_1") (pintype "passive"))
      (node (ref "C8") (pin "1") (pinfunction "1_1") (pintype "passive"))
      (node (ref "C9") (pin "1") (pinfunction "1_1") (pintype "passive"))
      (node (ref "IC3") (pin "10") (pinfunction "SCL_10") (pintype "input"))
      (node (ref "IC3") (pin "16") (pinfunction "VCC_16") (pintype "power_in"))
      (node (ref "IC5") (pin "10") (pinfunction "SCL_10") (pintype "input"))
      (node (ref "IC5") (pin "16") (pinfunction "VCC_16") (pintype "power_in"))
      (node (ref "IC7") (pin "3") (pinfunction "VCC_3") (pintype "power_in"))
      (node (ref "JP10") (pin "2") (pinfunction "2_2") (pintype "passive"))
      (node (ref "JP11") (pin "3") (pinfunction "3_3") (pintype "passive"))
      (node (ref "JP11") (pin "4") (pinfunction "4_4") (pintype "passive"))
      (node (ref "JP13") (pin "6") (pinfunction "6_6") (pintype "passive"))
      (node (ref "JP14") (pin "6") (pinfunction "6_6") (pintype "passive"))
      (node (ref "JP15") (pin "6") (pinfunction "6_6") (pintype "passive"))
      (node (ref "JP7") (pin "3") (pinfunction "3_3") (pintype "passive"))
      (node (ref "JP7") (pin "4") (pinfunction "4_4") (pintype "passive"))
      (node (ref "JP8") (pin "3") (pinfunction "3_3") (pintype "passive"))
      (node (ref "R19") (pin "2") (pinfunction "2_2") (pintype "passive"))
      (node (ref "R20") (pin "2") (pinfunction "2_2") (pintype "passive"))
      (node (ref "R21") (pin "2") (pinfunction "2_2") (pintype "passive"))
      (node (ref "R22") (pin "1") (pinfunction "1_1") (pintype "passive"))
      (node (ref "R23") (pin "1") (pinfunction "1_1") (pintype "passive"))
      (node (ref "R24") (pin "1") (pinfunction "1_1") (pintype "passive"))
      (node (ref "R25") (pin "1") (pinfunction "1_1") (pintype "passive"))
      (node (ref "R26") (pin "1") (pinfunction "1_1") (pintype "passive"))
      (node (ref "R27") (pin "1") (pinfunction "1_1") (pintype "passive"))
      (node (ref "R62") (pin "1") (pinfunction "1_1") (pintype "passive"))
      (node (ref "R63") (pin "1") (pinfunction "1_1") (pintype "passive"))
      (node (ref "SJ1") (pin "2") (pinfunction "2_2") (pintype "passive"))
      (node (ref "SJ10") (pin "2") (pinfunction "2_2") (pintype "passive"))
      (node (ref "SJ4") (pin "2") (pinfunction "2_2") (pintype "passive"))
      (node (ref "SJ7") (pin "2") (pinfunction "2_2") (pintype "passive"))
      (node (ref "U$1") (pin "5V2") (pinfunction "5V2_5V2") (pintype "power_in"))
      (node (ref "U$6") (pin "3") (pinfunction "VDD_3") (pintype "power_in"))
    )
    (net (code "3") (name "+12V") (class "Default")
      (node (ref "AP1509") (pin "1") (pinfunction "VIN_1") (pintype "bidirectional"))
      (node (ref "C10") (pin "1") (pinfunction "1_1") (pintype "passive"))
      (node (ref "C6") (pin "1") (pinfunction "1_1") (pintype "passive"))
      (node (ref "C7") (pin "1") (pinfunction "1_1") (pintype "passive"))
      (node (ref "IC10") (pin "5") (pinfunction "IN_5") (pintype "input"))
      (node (ref "IC6") (pin "4") (pinfunction "V+_4") (pintype "power_in"))
      (node (ref "IC9") (pin "4") (pinfunction "V+_4") (pintype "power_in"))
      (node (ref "J3") (pin "3") (pinfunction "3_3") (pintype "passive"))
      (node (ref "JP10") (pin "3") (pinfunction "3_3") (pintype "passive"))
      (node (ref "JP4") (pin "2") (pinfunction "2_2") (pintype "passive"))
      (node (ref "SJ11") (pin "2") (pinfunction "2_2") (pintype "passive"))
      (node (ref "SJ14") (pin "P$2") (pinfunction "2_P$2") (pintype "passive"))
      (node (ref "SJ2") (pin "2") (pinfunction "2_2") (pintype "passive"))
      (node (ref "SJ5") (pin "2") (pinfunction "2_2") (pintype "passive"))
      (node (ref "SJ8") (pin "2") (pinfunction "2_2") (pintype "passive"))
      (node (ref "U$2") (pin "6") (pinfunction "VDD_6") (pintype "power_in"))
      (node (ref "U$3") (pin "6") (pinfunction "VDD_6") (pintype "power_in"))
      (node (ref "U$4") (pin "6") (pinfunction "VDD_6") (pintype "power_in"))
      (node (ref "U$5") (pin "6") (pinfunction "VDD_6") (pintype "power_in"))
    )
    (net (code "4") (name "/AGND") (class "Default")
      (node (ref "U$1") (pin "AGND") (pinfunction "AGND_AGND") (pintype "power_in"))
    )
    (net (code "5") (name "/AVDD") (class "Default")
      (node (ref "U$1") (pin "AVDD") (pinfunction "AVDD_AVDD") (pintype "power_in"))
    )
    (net (code "6") (name "/CANH") (class "Default")
      (node (ref "IC7") (pin "7") (pinfunction "CANH_7") (pintype "bidirectional"))
      (node (ref "J1") (pin "1") (pinfunction "1_1") (pintype "passive"))
      (node (ref "J2") (pin "1") (pinfunction "1_1") (pintype "passive"))
      (node (ref "U$6") (pin "7") (pinfunction "CANH_7") (pintype "bidirectional"))
    )
    (net (code "7") (name "/CANL") (class "Default")
      (node (ref "IC7") (pin "6") (pinfunction "CANL_6") (pintype "bidirectional"))
      (node (ref "J1") (pin "2") (pinfunction "2_2") (pintype "passive"))
      (node (ref "J2") (pin "2") (pinfunction "2_2") (pintype "passive"))
      (node (ref "U$6") (pin "6") (pinfunction "CANL_6") (pintype "bidirectional"))
    )
    (net (code "8") (name "/G5V-3") (class "Default")
      (node (ref "U$1") (pin "PC12") (pinfunction "PC12_PC12") (pintype "bidirectional"))
    )
    (net (code "9") (name "/G5V-4") (class "Default")
      (node (ref "U$1") (pin "PD2") (pinfunction "PD2_PD2") (pintype "bidirectional"))
    )
    (net (code "10") (name "/G5V-5") (class "Default")
      (node (ref "U$1") (pin "PA15") (pinfunction "PA15_PA15") (pintype "bidirectional"))
    )
    (net (code "11") (name "/G5V-6") (class "Default")
      (node (ref "U$1") (pin "PF1-PH1") (pinfunction "PF1-PH1_PF1-PH1") (pintype "bidirectional"))
    )
    (net (code "12") (name "/TIN1") (class "Default")
      (node (ref "IC9") (pin "3") (pinfunction "+IN_3") (pintype "input"))
      (node (ref "U$1") (pin "PB2") (pinfunction "PB2_PB2") (pintype "bidirectional"))
      (node (ref "U$3") (pin "4") (pinfunction "I_4") (pintype "input"))
    )
    (net (code "13") (name "/TIN2") (class "Default")
      (node (ref "IC9") (pin "5") (pinfunction "+IN_5") (pintype "input"))
      (node (ref "U$1") (pin "PB1") (pinfunction "PB1_PB1") (pintype "bidirectional"))
      (node (ref "U$2") (pin "2") (pinfunction "I_2") (pintype "input"))
    )
    (net (code "14") (name "/TIN5") (class "Default")
      (node (ref "IC6") (pin "3") (pinfunction "+IN_3") (pintype "input"))
      (node (ref "U$1") (pin "PA4") (pinfunction "PA4_PA4") (pintype "bidirectional"))
      (node (ref "U$5") (pin "4") (pinfunction "I_4") (pintype "input"))
    )
    (net (code "15") (name "/TIN6") (class "Default")
      (node (ref "IC6") (pin "5") (pinfunction "+IN_5") (pintype "input"))
      (node (ref "U$1") (pin "PC0") (pinfunction "PC0_PC0") (pintype "bidirectional"))
      (node (ref "U$4") (pin "2") (pinfunction "I_2") (pintype "input"))
    )
    (net (code "16") (name "/TIN7") (class "Default")
      (node (ref "IC6") (pin "10") (pinfunction "+IN_10") (pintype "input"))
      (node (ref "U$1") (pin "PC3") (pinfunction "PC3_PC3") (pintype "bidirectional"))
      (node (ref "U$4") (pin "4") (pinfunction "I_4") (pintype "input"))
    )
    (net (code "17") (name "/TIN8") (class "Default")
      (node (ref "IC6") (pin "12") (pinfunction "+IN_12") (pintype "input"))
      (node (ref "U$1") (pin "PA0") (pinfunction "PA0_PA0") (pintype "bidirectional"))
      (node (ref "U$5") (pin "2") (pinfunction "I_2") (pintype "input"))
    )
    (net (code "18") (name "/U5V") (class "Default")
      (node (ref "U$1") (pin "U5V") (pinfunction "U5V_U5V") (pintype "power_in"))
    )
    (net (code "19") (name "/VBAT") (class "Default")
      (node (ref "U$1") (pin "VBAT") (pinfunction "VBAT_VBAT") (pintype "power_in"))
    )
    (net (code "20") (name "/VDD") (class "Default")
      (node (ref "U$1") (pin "VDD") (pinfunction "VDD_VDD") (pintype "power_in"))
    )
    (net (code "21") (name "CANRX") (class "Default")
      (node (ref "IC7") (pin "4") (pinfunction "RXD_4") (pintype "output"))
      (node (ref "U$1") (pin "PB8") (pinfunction "PB8_PB8") (pintype "bidirectional"))
      (node (ref "U$6") (pin "4") (pinfunction "RXD_4") (pintype "bidirectional"))
    )
    (net (code "22") (name "CANTX") (class "Default")
      (node (ref "IC7") (pin "1") (pinfunction "TXD_1") (pintype "input"))
      (node (ref "U$1") (pin "PB9") (pinfunction "PB9_PB9") (pintype "bidirectional"))
      (node (ref "U$6") (pin "1") (pinfunction "TXD_1") (pintype "bidirectional"))
    )
    (net (code "23") (name "E_CS") (class "Default")
      (node (ref "JP9") (pin "4") (pinfunction "4_4") (pintype "passive"))
      (node (ref "R23") (pin "2") (pinfunction "2_2") (pintype "passive"))
      (node (ref "U$1") (pin "PC10") (pinfunction "PC10_PC10") (pintype "bidirectional"))
    )
    (net (code "24") (name "E_LAT") (class "Default")
      (node (ref "JP10") (pin "1") (pinfunction "1_1") (pintype "passive"))
      (node (ref "R22") (pin "2") (pinfunction "2_2") (pintype "passive"))
      (node (ref "U$1") (pin "PC11") (pinfunction "PC11_PC11") (pintype "bidirectional"))
    )
    (net (code "25") (name "GND") (class "Default")
      (node (ref "AP1509") (pin "4") (pinfunction "SD_4") (pintype "bidirectional"))
      (node (ref "AP1509") (pin "5") (pinfunction "GND1_5") (pintype "power_in"))
      (node (ref "AP1509") (pin "6") (pinfunction "GND2_6") (pintype "power_in"))
      (node (ref "AP1509") (pin "7") (pinfunction "GND3_7") (pintype "power_in"))
      (node (ref "AP1509") (pin "8") (pinfunction "GND4_8") (pintype "power_in"))
      (node (ref "C1") (pin "2") (pinfunction "2_2") (pintype "passive"))
      (node (ref "C10") (pin "2") (pinfunction "2_2") (pintype "passive"))
      (node (ref "C11") (pin "2") (pinfunction "2_2") (pintype "passive"))
      (node (ref "C2") (pin "-") (pinfunction "-_-") (pintype "passive"))
      (node (ref "C3") (pin "2") (pinfunction "2_2") (pintype "passive"))
      (node (ref "C4") (pin "2") (pinfunction "2_2") (pintype "passive"))
      (node (ref "C5") (pin "2") (pinfunction "2_2") (pintype "passive"))
      (node (ref "C6") (pin "2") (pinfunction "2_2") (pintype "passive"))
      (node (ref "C7") (pin "2") (pinfunction "2_2") (pintype "passive"))
      (node (ref "C8") (pin "2") (pinfunction "2_2") (pintype "passive"))
      (node (ref "C9") (pin "2") (pinfunction "2_2") (pintype "passive"))
      (node (ref "D1") (pin "A") (pinfunction "A_A") (pintype "passive"))
      (node (ref "IC1") (pin "6") (pinfunction "INH_6") (pintype "input"))
      (node (ref "IC1") (pin "8") (pinfunction "GND_8") (pintype "power_in"))
      (node (ref "IC10") (pin "2") (pinfunction "GNDSIG_2") (pintype "input"))
      (node (ref "IC10") (pin "3") (pinfunction "~{ON/OFF}_3") (pintype "input"))
      (node (ref "IC10") (pin "4") (pinfunction "GND_4") (pintype "power_in"))
      (node (ref "IC3") (pin "13") (pinfunction "G_13") (pintype "input"))
      (node (ref "IC3") (pin "8") (pinfunction "GND_8") (pintype "power_in"))
      (node (ref "IC4") (pin "6") (pinfunction "INH_6") (pintype "input"))
      (node (ref "IC4") (pin "8") (pinfunction "GND_8") (pintype "power_in"))
      (node (ref "IC5") (pin "13") (pinfunction "G_13") (pintype "input"))
      (node (ref "IC5") (pin "8") (pinfunction "GND_8") (pintype "power_in"))
      (node (ref "IC6") (pin "11") (pinfunction "V-_11") (pintype "power_in"))
      (node (ref "IC7") (pin "2") (pinfunction "GND_2") (pintype "power_in"))
      (node (ref "IC9") (pin "11") (pinfunction "V-_11") (pintype "power_in"))
      (node (ref "J1") (pin "3") (pinfunction "3_3") (pintype "passive"))
      (node (ref "J1") (pin "6") (pinfunction "6_6") (pintype "passive"))
      (node (ref "J1") (pin "7") (pinfunction "7_7") (pintype "passive"))
      (node (ref "J2") (pin "3") (pinfunction "3_3") (pintype "passive"))
      (node (ref "J2") (pin "6") (pinfunction "6_6") (pintype "passive"))
      (node (ref "J2") (pin "7") (pinfunction "7_7") (pintype "passive"))
      (node (ref "J3") (pin "1") (pinfunction "1_1") (pintype "passive"))
      (node (ref "JP10") (pin "4") (pinfunction "4_4") (pintype "passive"))
      (node (ref "JP11") (pin "5") (pinfunction "5_5") (pintype "passive"))
      (node (ref "JP11") (pin "6") (pinfunction "6_6") (pintype "passive"))
      (node (ref "JP13") (pin "5") (pinfunction "5_5") (pintype "passive"))
      (node (ref "JP14") (pin "5") (pinfunction "5_5") (pintype "passive"))
      (node (ref "JP15") (pin "5") (pinfunction "5_5") (pintype "passive"))
      (node (ref "JP7") (pin "5") (pinfunction "5_5") (pintype "passive"))
      (node (ref "JP7") (pin "6") (pinfunction "6_6") (pintype "passive"))
      (node (ref "JP8") (pin "4") (pinfunction "4_4") (pintype "passive"))
      (node (ref "Q1") (pin "2") (pinfunction "S_2") (pintype "passive"))
      (node (ref "Q10") (pin "2") (pinfunction "S_2") (pintype "passive"))
      (node (ref "Q11") (pin "2") (pinfunction "S_2") (pintype "passive"))
      (node (ref "Q12") (pin "2") (pinfunction "S_2") (pintype "passive"))
      (node (ref "Q13") (pin "2") (pinfunction "S_2") (pintype "passive"))
      (node (ref "Q14") (pin "2") (pinfunction "S_2") (pintype "passive"))
      (node (ref "Q15") (pin "2") (pinfunction "S_2") (pintype "passive"))
      (node (ref "Q16") (pin "2") (pinfunction "S_2") (pintype "passive"))
      (node (ref "Q2") (pin "2") (pinfunction "S_2") (pintype "passive"))
      (node (ref "Q3") (pin "2") (pinfunction "S_2") (pintype "passive"))
      (node (ref "Q4") (pin "2") (pinfunction "S_2") (pintype "passive"))
      (node (ref "Q5") (pin "2") (pinfunction "S_2") (pintype "passive"))
      (node (ref "Q6") (pin "2") (pinfunction "S_2") (pintype "passive"))
      (node (ref "Q7") (pin "2") (pinfunction "S_2") (pintype "passive"))
      (node (ref "Q8") (pin "2") (pinfunction "S_2") (pintype "passive"))
      (node (ref "Q9") (pin "2") (pinfunction "S_2") (pintype "passive"))
      (node (ref "R2") (pin "1") (pinfunction "1_1") (pintype "passive"))
      (node (ref "R61") (pin "2") (pinfunction "2_2") (pintype "passive"))
      (node (ref "SJ12") (pin "2") (pinfunction "2_2") (pintype "passive"))
      (node (ref "SJ3") (pin "2") (pinfunction "2_2") (pintype "passive"))
      (node (ref "SJ6") (pin "2") (pinfunction "2_2") (pintype "passive"))
      (node (ref "SJ9") (pin "2") (pinfunction "2_2") (pintype "passive"))
      (node (ref "U$1") (pin "GND3") (pinfunction "GND3_GND3") (pintype "power_in"))
      (node (ref "U$1") (pin "GND4") (pinfunction "GND4_GND4") (pintype "power_in"))
      (node (ref "U$1") (pin "GND5") (pinfunction "GND5_GND5") (pintype "power_in"))
      (node (ref "U$1") (pin "GND6") (pinfunction "GND6_GND6") (pintype "power_in"))
      (node (ref "U$1") (pin "GND7") (pinfunction "GND7_GND7") (pintype "power_in"))
      (node (ref "U$1") (pin "GND8") (pinfunction "GND8_GND8") (pintype "power_in"))
      (node (ref "U$2") (pin "3") (pinfunction "VSS_3") (pintype "power_in"))
      (node (ref "U$3") (pin "3") (pinfunction "VSS_3") (pintype "power_in"))
      (node (ref "U$4") (pin "3") (pinfunction "VSS_3") (pintype "power_in"))
      (node (ref "U$5") (pin "3") (pinfunction "VSS_3") (pintype "power_in"))
      (node (ref "U$6") (pin "2") (pinfunction "VSS_2") (pintype "power_in"))
    )
    (net (code "26") (name "I2CSCL") (class "Default")
      (node (ref "JP8") (pin "2") (pinfunction "2_2") (pintype "passive"))
      (node (ref "R63") (pin "2") (pinfunction "2_2") (pintype "passive"))
      (node (ref "U$1") (pin "PB6") (pinfunction "PB6_PB6") (pintype "bidirectional"))
    )
    (net (code "27") (name "I2CSDA") (class "Default")
      (node (ref "JP8") (pin "1") (pinfunction "1_1") (pintype "passive"))
      (node (ref "R62") (pin "2") (pinfunction "2_2") (pintype "passive"))
      (node (ref "U$1") (pin "PB7") (pinfunction "PB7_PB7") (pintype "bidirectional"))
    )
    (net (code "28") (name "ILAT") (class "Default")
      (node (ref "IC1") (pin "15") (pinfunction "SH/~{LD}_15") (pintype "input"))
      (node (ref "IC4") (pin "15") (pinfunction "SH/~{LD}_15") (pintype "input"))
      (node (ref "U$1") (pin "PA6") (pinfunction "PA6_PA6") (pintype "bidirectional"))
    )
    (net (code "29") (name "MISO") (class "Default")
      (node (ref "JP9") (pin "1") (pinfunction "1_1") (pintype "passive"))
      (node (ref "U$1") (pin "PB4") (pinfunction "PB4_PB4") (pintype "bidirectional"))
    )
    (net (code "30") (name "MISO2") (class "Default")
      (node (ref "IC4") (pin "13") (pinfunction "QH_13") (pintype "output"))
      (node (ref "SJ13") (pin "P$2") (pinfunction "2_P$2") (pintype "passive"))
      (node (ref "U$1") (pin "PC2") (pinfunction "PC2_PC2") (pintype "bidirectional"))
    )
    (net (code "31") (name "MOSI") (class "Default")
      (node (ref "IC5") (pin "14") (pinfunction "SER_14") (pintype "input"))
      (node (ref "R20") (pin "1") (pinfunction "1_1") (pintype "passive"))
      (node (ref "SJ15") (pin "1") (pinfunction "1_1") (pintype "passive"))
      (node (ref "SJ17") (pin "P$2") (pinfunction "2_P$2") (pintype "passive"))
      (node (ref "U$1") (pin "PB5") (pinfunction "PB5_PB5") (pintype "bidirectional"))
    )
    (net (code "32") (name "Net-(AP1509-VOUT)") (class "Default")
      (node (ref "AP1509") (pin "2") (pinfunction "VOUT_2") (pintype "bidirectional"))
      (node (ref "D1") (pin "C") (pinfunction "C_C") (pintype "passive"))
      (node (ref "IC10") (pin "7") (pinfunction "OUT_7") (pintype "passive"))
      (node (ref "L1") (pin "2") (pinfunction "2_2") (pintype "passive"))
    )
    (net (code "33") (name "Net-(D2-PadA)") (class "Default")
      (node (ref "D2") (pin "A") (pinfunction "A_A") (pintype "passive"))
      (node (ref "JP4") (pin "4") (pinfunction "4_4") (pintype "passive"))
    )
    (net (code "34") (name "Net-(D2-PadC)") (class "Default")
      (node (ref "D2") (pin "C") (pinfunction "C_C") (pintype "passive"))
      (node (ref "JP4") (pin "1") (pinfunction "1_1") (pintype "passive"))
    )
    (net (code "35") (name "Net-(IC1A-A)") (class "Default")
      (node (ref "IC1") (pin "2") (pinfunction "A_2") (pintype "input"))
      (node (ref "R36") (pin "1") (pinfunction "1_1") (pintype "passive"))
      (node (ref "RN4") (pin "9") (pinfunction "2_9") (pintype "passive"))
    )
    (net (code "36") (name "Net-(IC1A-B)") (class "Default")
      (node (ref "IC1") (pin "3") (pinfunction "B_3") (pintype "input"))
      (node (ref "R37") (pin "1") (pinfunction "1_1") (pintype "passive"))
      (node (ref "RN4") (pin "10") (pinfunction "2_10") (pintype "passive"))
    )
    (net (code "37") (name "Net-(IC1A-C)") (class "Default")
      (node (ref "IC1") (pin "4") (pinfunction "C_4") (pintype "input"))
      (node (ref "R38") (pin "1") (pinfunction "1_1") (pintype "passive"))
      (node (ref "RN4") (pin "11") (pinfunction "2_11") (pintype "passive"))
    )
    (net (code "38") (name "Net-(IC1A-D)") (class "Default")
      (node (ref "IC1") (pin "5") (pinfunction "D_5") (pintype "input"))
      (node (ref "R39") (pin "1") (pinfunction "1_1") (pintype "passive"))
      (node (ref "RN4") (pin "12") (pinfunction "2_12") (pintype "passive"))
    )
    (net (code "39") (name "Net-(IC1A-E)") (class "Default")
      (node (ref "IC1") (pin "10") (pinfunction "E_10") (pintype "input"))
      (node (ref "R41") (pin "1") (pinfunction "1_1") (pintype "passive"))
      (node (ref "RN4") (pin "13") (pinfunction "2_13") (pintype "passive"))
    )
    (net (code "40") (name "Net-(IC1A-F)") (class "Default")
      (node (ref "IC1") (pin "11") (pinfunction "F_11") (pintype "input"))
      (node (ref "R42") (pin "1") (pinfunction "1_1") (pintype "passive"))
      (node (ref "RN4") (pin "14") (pinfunction "2_14") (pintype "passive"))
    )
    (net (code "41") (name "Net-(IC1A-G)") (class "Default")
      (node (ref "IC1") (pin "12") (pinfunction "G_12") (pintype "input"))
      (node (ref "R43") (pin "1") (pinfunction "1_1") (pintype "passive"))
      (node (ref "RN4") (pin "15") (pinfunction "2_15") (pintype "passive"))
    )
    (net (code "42") (name "Net-(IC1A-H)") (class "Default")
      (node (ref "IC1") (pin "14") (pinfunction "H_14") (pintype "input"))
      (node (ref "R44") (pin "1") (pinfunction "1_1") (pintype "passive"))
      (node (ref "RN4") (pin "16") (pinfunction "2_16") (pintype "passive"))
    )
    (net (code "43") (name "Net-(IC2-CD+)") (class "Default")
      (node (ref "IC2") (pin "10") (pinfunction "CD+_10") (pintype "passive"))
      (node (ref "SJ4") (pin "1") (pinfunction "1_1") (pintype "passive"))
      (node (ref "SJ5") (pin "1") (pinfunction "1_1") (pintype "passive"))
      (node (ref "SJ6") (pin "1") (pinfunction "1_1") (pintype "passive"))
    )
    (net (code "44") (name "Net-(IC2-GND)") (class "Default")
      (node (ref "IC2") (pin "9") (pinfunction "GND_9") (pintype "power_in"))
      (node (ref "SJ1") (pin "1") (pinfunction "1_1") (pintype "passive"))
      (node (ref "SJ2") (pin "1") (pinfunction "1_1") (pintype "passive"))
      (node (ref "SJ3") (pin "1") (pinfunction "1_1") (pintype "passive"))
    )
    (net (code "45") (name "Net-(IC2-I1)") (class "Default")
      (node (ref "IC2") (pin "1") (pinfunction "I1_1") (pintype "input"))
      (node (ref "IC5") (pin "15") (pinfunction "QA_15") (pintype "tri_state"))
      (node (ref "R3") (pin "1") (pinfunction "1_1") (pintype "passive"))
    )
    (net (code "46") (name "Net-(IC2-I2)") (class "Default")
      (node (ref "IC2") (pin "2") (pinfunction "I2_2") (pintype "input"))
      (node (ref "IC5") (pin "1") (pinfunction "QB_1") (pintype "tri_state"))
      (node (ref "R4") (pin "1") (pinfunction "1_1") (pintype "passive"))
    )
    (net (code "47") (name "Net-(IC2-I3)") (class "Default")
      (node (ref "IC2") (pin "3") (pinfunction "I3_3") (pintype "input"))
      (node (ref "IC5") (pin "2") (pinfunction "QC_2") (pintype "tri_state"))
      (node (ref "R5") (pin "1") (pinfunction "1_1") (pintype "passive"))
    )
    (net (code "48") (name "Net-(IC2-I4)") (class "Default")
      (node (ref "IC2") (pin "4") (pinfunction "I4_4") (pintype "input"))
      (node (ref "IC5") (pin "3") (pinfunction "QD_3") (pintype "tri_state"))
      (node (ref "R6") (pin "1") (pinfunction "1_1") (pintype "passive"))
    )
    (net (code "49") (name "Net-(IC2-I5)") (class "Default")
      (node (ref "IC2") (pin "5") (pinfunction "I5_5") (pintype "input"))
      (node (ref "IC5") (pin "4") (pinfunction "QE_4") (pintype "tri_state"))
      (node (ref "R7") (pin "1") (pinfunction "1_1") (pintype "passive"))
    )
    (net (code "50") (name "Net-(IC2-I6)") (class "Default")
      (node (ref "IC2") (pin "6") (pinfunction "I6_6") (pintype "input"))
      (node (ref "IC5") (pin "5") (pinfunction "QF_5") (pintype "tri_state"))
      (node (ref "R8") (pin "1") (pinfunction "1_1") (pintype "passive"))
    )
    (net (code "51") (name "Net-(IC2-I7)") (class "Default")
      (node (ref "IC2") (pin "7") (pinfunction "I7_7") (pintype "input"))
      (node (ref "IC5") (pin "6") (pinfunction "QG_6") (pintype "tri_state"))
      (node (ref "R9") (pin "1") (pinfunction "1_1") (pintype "passive"))
    )
    (net (code "52") (name "Net-(IC2-I8)") (class "Default")
      (node (ref "IC2") (pin "8") (pinfunction "I8_8") (pintype "input"))
      (node (ref "IC5") (pin "7") (pinfunction "QH_7") (pintype "tri_state"))
      (node (ref "R10") (pin "1") (pinfunction "1_1") (pintype "passive"))
    )
    (net (code "53") (name "Net-(IC2-O1)") (class "Default")
      (node (ref "IC2") (pin "18") (pinfunction "O1_18") (pintype "open_collector"))
      (node (ref "JP1") (pin "1") (pinfunction "1_1") (pintype "passive"))
      (node (ref "Q1") (pin "3") (pinfunction "D_3") (pintype "passive"))
    )
    (net (code "54") (name "Net-(IC2-O2)") (class "Default")
      (node (ref "IC2") (pin "17") (pinfunction "O2_17") (pintype "open_collector"))
      (node (ref "JP1") (pin "2") (pinfunction "2_2") (pintype "passive"))
      (node (ref "Q2") (pin "3") (pinfunction "D_3") (pintype "passive"))
    )
    (net (code "55") (name "Net-(IC2-O3)") (class "Default")
      (node (ref "IC2") (pin "16") (pinfunction "O3_16") (pintype "open_collector"))
      (node (ref "JP1") (pin "3") (pinfunction "3_3") (pintype "passive"))
      (node (ref "Q3") (pin "3") (pinfunction "D_3") (pintype "passive"))
    )
    (net (code "56") (name "Net-(IC2-O4)") (class "Default")
      (node (ref "IC2") (pin "15") (pinfunction "O4_15") (pintype "open_collector"))
      (node (ref "JP1") (pin "4") (pinfunction "4_4") (pintype "passive"))
      (node (ref "Q4") (pin "3") (pinfunction "D_3") (pintype "passive"))
    )
    (net (code "57") (name "Net-(IC2-O5)") (class "Default")
      (node (ref "IC2") (pin "14") (pinfunction "O5_14") (pintype "open_collector"))
      (node (ref "JP1") (pin "5") (pinfunction "5_5") (pintype "passive"))
      (node (ref "Q5") (pin "3") (pinfunction "D_3") (pintype "passive"))
    )
    (net (code "58") (name "Net-(IC2-O6)") (class "Default")
      (node (ref "IC2") (pin "13") (pinfunction "O6_13") (pintype "open_collector"))
      (node (ref "JP1") (pin "6") (pinfunction "6_6") (pintype "passive"))
      (node (ref "Q6") (pin "3") (pinfunction "D_3") (pintype "passive"))
    )
    (net (code "59") (name "Net-(IC2-O7)") (class "Default")
      (node (ref "IC2") (pin "12") (pinfunction "O7_12") (pintype "open_collector"))
      (node (ref "JP1") (pin "7") (pinfunction "7_7") (pintype "passive"))
      (node (ref "Q7") (pin "3") (pinfunction "D_3") (pintype "passive"))
    )
    (net (code "60") (name "Net-(IC2-O8)") (class "Default")
      (node (ref "IC2") (pin "11") (pinfunction "O8_11") (pintype "open_collector"))
      (node (ref "JP1") (pin "8") (pinfunction "8_8") (pintype "passive"))
      (node (ref "Q8") (pin "3") (pinfunction "D_3") (pintype "passive"))
    )
    (net (code "61") (name "Net-(IC3A-QA)") (class "Default")
      (node (ref "IC3") (pin "15") (pinfunction "QA_15") (pintype "tri_state"))
      (node (ref "IC8") (pin "1") (pinfunction "I1_1") (pintype "input"))
      (node (ref "R11") (pin "1") (pinfunction "1_1") (pintype "passive"))
    )
    (net (code "62") (name "Net-(IC3A-QB)") (class "Default")
      (node (ref "IC3") (pin "1") (pinfunction "QB_1") (pintype "tri_state"))
      (node (ref "IC8") (pin "2") (pinfunction "I2_2") (pintype "input"))
      (node (ref "R12") (pin "1") (pinfunction "1_1") (pintype "passive"))
    )
    (net (code "63") (name "Net-(IC3A-QC)") (class "Default")
      (node (ref "IC3") (pin "2") (pinfunction "QC_2") (pintype "tri_state"))
      (node (ref "IC8") (pin "3") (pinfunction "I3_3") (pintype "input"))
      (node (ref "R13") (pin "1") (pinfunction "1_1") (pintype "passive"))
    )
    (net (code "64") (name "Net-(IC3A-QD)") (class "Default")
      (node (ref "IC3") (pin "3") (pinfunction "QD_3") (pintype "tri_state"))
      (node (ref "IC8") (pin "4") (pinfunction "I4_4") (pintype "input"))
      (node (ref "R14") (pin "1") (pinfunction "1_1") (pintype "passive"))
    )
    (net (code "65") (name "Net-(IC3A-QE)") (class "Default")
      (node (ref "IC3") (pin "4") (pinfunction "QE_4") (pintype "tri_state"))
      (node (ref "IC8") (pin "5") (pinfunction "I5_5") (pintype "input"))
      (node (ref "R15") (pin "1") (pinfunction "1_1") (pintype "passive"))
    )
    (net (code "66") (name "Net-(IC3A-QF)") (class "Default")
      (node (ref "IC3") (pin "5") (pinfunction "QF_5") (pintype "tri_state"))
      (node (ref "IC8") (pin "6") (pinfunction "I6_6") (pintype "input"))
      (node (ref "R16") (pin "1") (pinfunction "1_1") (pintype "passive"))
    )
    (net (code "67") (name "Net-(IC3A-QG)") (class "Default")
      (node (ref "IC3") (pin "6") (pinfunction "QG_6") (pintype "tri_state"))
      (node (ref "IC8") (pin "7") (pinfunction "I7_7") (pintype "input"))
      (node (ref "R17") (pin "1") (pinfunction "1_1") (pintype "passive"))
    )
    (net (code "68") (name "Net-(IC3A-QH)") (class "Default")
      (node (ref "IC3") (pin "7") (pinfunction "QH_7") (pintype "tri_state"))
      (node (ref "IC8") (pin "8") (pinfunction "I8_8") (pintype "input"))
      (node (ref "R18") (pin "1") (pinfunction "1_1") (pintype "passive"))
    )
    (net (code "69") (name "Net-(IC4A-A)") (class "Default")
      (node (ref "IC4") (pin "2") (pinfunction "A_2") (pintype "input"))
      (node (ref "R28") (pin "1") (pinfunction "1_1") (pintype "passive"))
      (node (ref "RN1") (pin "9") (pinfunction "2_9") (pintype "passive"))
    )
    (net (code "70") (name "Net-(IC4A-B)") (class "Default")
      (node (ref "IC4") (pin "3") (pinfunction "B_3") (pintype "input"))
      (node (ref "R29") (pin "1") (pinfunction "1_1") (pintype "passive"))
      (node (ref "RN1") (pin "10") (pinfunction "2_10") (pintype "passive"))
    )
    (net (code "71") (name "Net-(IC4A-C)") (class "Default")
      (node (ref "IC4") (pin "4") (pinfunction "C_4") (pintype "input"))
      (node (ref "R30") (pin "1") (pinfunction "1_1") (pintype "passive"))
      (node (ref "RN1") (pin "11") (pinfunction "2_11") (pintype "passive"))
    )
    (net (code "72") (name "Net-(IC4A-D)") (class "Default")
      (node (ref "IC4") (pin "5") (pinfunction "D_5") (pintype "input"))
      (node (ref "R31") (pin "1") (pinfunction "1_1") (pintype "passive"))
      (node (ref "RN1") (pin "12") (pinfunction "2_12") (pintype "passive"))
    )
    (net (code "73") (name "Net-(IC4A-E)") (class "Default")
      (node (ref "IC4") (pin "10") (pinfunction "E_10") (pintype "input"))
      (node (ref "R32") (pin "1") (pinfunction "1_1") (pintype "passive"))
      (node (ref "RN1") (pin "13") (pinfunction "2_13") (pintype "passive"))
    )
    (net (code "74") (name "Net-(IC4A-F)") (class "Default")
      (node (ref "IC4") (pin "11") (pinfunction "F_11") (pintype "input"))
      (node (ref "R33") (pin "1") (pinfunction "1_1") (pintype "passive"))
      (node (ref "RN1") (pin "14") (pinfunction "2_14") (pintype "passive"))
    )
    (net (code "75") (name "Net-(IC4A-G)") (class "Default")
      (node (ref "IC4") (pin "12") (pinfunction "G_12") (pintype "input"))
      (node (ref "R34") (pin "1") (pinfunction "1_1") (pintype "passive"))
      (node (ref "RN1") (pin "15") (pinfunction "2_15") (pintype "passive"))
    )
    (net (code "76") (name "Net-(IC4A-H)") (class "Default")
      (node (ref "IC4") (pin "14") (pinfunction "H_14") (pintype "input"))
      (node (ref "R35") (pin "1") (pinfunction "1_1") (pintype "passive"))
      (node (ref "RN1") (pin "16") (pinfunction "2_16") (pintype "passive"))
    )
    (net (code "77") (name "Net-(IC6A--IN)") (class "Default")
      (node (ref "IC6") (pin "13") (pinfunction "-IN_13") (pintype "input"))
      (node (ref "IC6") (pin "2") (pinfunction "-IN_2") (pintype "input"))
      (node (ref "IC6") (pin "6") (pinfunction "-IN_6") (pintype "input"))
      (node (ref "IC6") (pin "9") (pinfunction "-IN_9") (pintype "input"))
      (node (ref "IC9") (pin "13") (pinfunction "-IN_13") (pintype "input"))
      (node (ref "IC9") (pin "2") (pinfunction "-IN_2") (pintype "input"))
      (node (ref "IC9") (pin "6") (pinfunction "-IN_6") (pintype "input"))
      (node (ref "IC9") (pin "9") (pinfunction "-IN_9") (pintype "input"))
      (node (ref "R1") (pin "1") (pinfunction "1_1") (pintype "passive"))
      (node (ref "R2") (pin "2") (pinfunction "2_2") (pintype "passive"))
    )
    (net (code "78") (name "Net-(IC6A-OUT)") (class "Default")
      (node (ref "IC6") (pin "1") (pinfunction "OUT_1") (pintype "output"))
      (node (ref "JP15") (pin "3") (pinfunction "3_3") (pintype "passive"))
      (node (ref "JP5") (pin "3") (pinfunction "3_3") (pintype "passive"))
      (node (ref "U$5") (pin "5") (pinfunction "O_5") (pintype "output"))
    )
    (net (code "79") (name "Net-(IC6B-OUT)") (class "Default")
      (node (ref "IC6") (pin "7") (pinfunction "OUT_7") (pintype "output"))
      (node (ref "JP15") (pin "1") (pinfunction "1_1") (pintype "passive"))
      (node (ref "JP5") (pin "1") (pinfunction "1_1") (pintype "passive"))
      (node (ref "U$4") (pin "7") (pinfunction "O_7") (pintype "output"))
    )
    (net (code "80") (name "Net-(IC6C-OUT)") (class "Default")
      (node (ref "IC6") (pin "8") (pinfunction "OUT_8") (pintype "output"))
      (node (ref "JP15") (pin "2") (pinfunction "2_2") (pintype "passive"))
      (node (ref "JP5") (pin "2") (pinfunction "2_2") (pintype "passive"))
      (node (ref "U$4") (pin "5") (pinfunction "O_5") (pintype "output"))
    )
    (net (code "81") (name "Net-(IC6D-OUT)") (class "Default")
      (node (ref "IC6") (pin "14") (pinfunction "OUT_14") (pintype "output"))
      (node (ref "JP15") (pin "4") (pinfunction "4_4") (pintype "passive"))
      (node (ref "JP5") (pin "4") (pinfunction "4_4") (pintype "passive"))
      (node (ref "U$5") (pin "7") (pinfunction "O_7") (pintype "output"))
    )
    (net (code "82") (name "Net-(IC7-RS)") (class "Default")
      (node (ref "IC7") (pin "8") (pinfunction "RS_8") (pintype "input"))
      (node (ref "R61") (pin "1") (pinfunction "1_1") (pintype "passive"))
      (node (ref "U$6") (pin "8") (pinfunction "RS_8") (pintype "bidirectional"))
    )
    (net (code "83") (name "Net-(IC7-VREF)") (class "Default")
      (node (ref "IC7") (pin "5") (pinfunction "VREF_5") (pintype "output"))
      (node (ref "SJ18") (pin "P$2") (pinfunction "2_P$2") (pintype "passive"))
      (node (ref "U$6") (pin "5") (pinfunction "VREF_5") (pintype "bidirectional"))
    )
    (net (code "84") (name "Net-(IC8-CD+)") (class "Default")
      (node (ref "IC8") (pin "10") (pinfunction "CD+_10") (pintype "passive"))
      (node (ref "SJ10") (pin "1") (pinfunction "1_1") (pintype "passive"))
      (node (ref "SJ11") (pin "1") (pinfunction "1_1") (pintype "passive"))
      (node (ref "SJ12") (pin "1") (pinfunction "1_1") (pintype "passive"))
    )
    (net (code "85") (name "Net-(IC8-GND)") (class "Default")
      (node (ref "IC8") (pin "9") (pinfunction "GND_9") (pintype "power_in"))
      (node (ref "SJ7") (pin "1") (pinfunction "1_1") (pintype "passive"))
      (node (ref "SJ8") (pin "1") (pinfunction "1_1") (pintype "passive"))
      (node (ref "SJ9") (pin "1") (pinfunction "1_1") (pintype "passive"))
    )
    (net (code "86") (name "Net-(IC8-O1)") (class "Default")
      (node (ref "IC8") (pin "18") (pinfunction "O1_18") (pintype "open_collector"))
      (node (ref "JP6") (pin "1") (pinfunction "1_1") (pintype "passive"))
      (node (ref "Q9") (pin "3") (pinfunction "D_3") (pintype "passive"))
    )
    (net (code "87") (name "Net-(IC8-O2)") (class "Default")
      (node (ref "IC8") (pin "17") (pinfunction "O2_17") (pintype "open_collector"))
      (node (ref "JP6") (pin "2") (pinfunction "2_2") (pintype "passive"))
      (node (ref "Q10") (pin "3") (pinfunction "D_3") (pintype "passive"))
    )
    (net (code "88") (name "Net-(IC8-O3)") (class "Default")
      (node (ref "IC8") (pin "16") (pinfunction "O3_16") (pintype "open_collector"))
      (node (ref "JP6") (pin "3") (pinfunction "3_3") (pintype "passive"))
      (node (ref "Q11") (pin "3") (pinfunction "D_3") (pintype "passive"))
    )
    (net (code "89") (name "Net-(IC8-O4)") (class "Default")
      (node (ref "IC8") (pin "15") (pinfunction "O4_15") (pintype "open_collector"))
      (node (ref "JP6") (pin "4") (pinfunction "4_4") (pintype "passive"))
      (node (ref "Q12") (pin "3") (pinfunction "D_3") (pintype "passive"))
    )
    (net (code "90") (name "Net-(IC8-O5)") (class "Default")
      (node (ref "IC8") (pin "14") (pinfunction "O5_14") (pintype "open_collector"))
      (node (ref "JP6") (pin "5") (pinfunction "5_5") (pintype "passive"))
      (node (ref "Q13") (pin "3") (pinfunction "D_3") (pintype "passive"))
    )
    (net (code "91") (name "Net-(IC8-O6)") (class "Default")
      (node (ref "IC8") (pin "13") (pinfunction "O6_13") (pintype "open_collector"))
      (node (ref "JP6") (pin "6") (pinfunction "6_6") (pintype "passive"))
      (node (ref "Q14") (pin "3") (pinfunction "D_3") (pintype "passive"))
    )
    (net (code "92") (name "Net-(IC8-O7)") (class "Default")
      (node (ref "IC8") (pin "12") (pinfunction "O7_12") (pintype "open_collector"))
      (node (ref "JP6") (pin "7") (pinfunction "7_7") (pintype "passive"))
      (node (ref "Q15") (pin "3") (pinfunction "D_3") (pintype "passive"))
    )
    (net (code "93") (name "Net-(IC8-O8)") (class "Default")
      (node (ref "IC8") (pin "11") (pinfunction "O8_11") (pintype "open_collector"))
      (node (ref "JP6") (pin "8") (pinfunction "8_8") (pintype "passive"))
      (node (ref "Q16") (pin "3") (pinfunction "D_3") (pintype "passive"))
    )
    (net (code "94") (name "Net-(IC9A-OUT)") (class "Default")
      (node (ref "IC9") (pin "1") (pinfunction "OUT_1") (pintype "output"))
      (node (ref "JP15") (pin "9") (pinfunction "9_9") (pintype "passive"))
      (node (ref "JP5") (pin "7") (pinfunction "7_7") (pintype "passive"))
      (node (ref "U$3") (pin "5") (pinfunction "O_5") (pintype "output"))
    )
    (net (code "95") (name "Net-(IC9B-OUT)") (class "Default")
      (node (ref "IC9") (pin "7") (pinfunction "OUT_7") (pintype "output"))
      (node (ref "JP15") (pin "7") (pinfunction "7_7") (pintype "passive"))
      (node (ref "JP5") (pin "5") (pinfunction "5_5") (pintype "passive"))
      (node (ref "U$2") (pin "7") (pinfunction "O_7") (pintype "output"))
    )
    (net (code "96") (name "Net-(IC9C-OUT)") (class "Default")
      (node (ref "IC9") (pin "8") (pinfunction "OUT_8") (pintype "output"))
      (node (ref "JP15") (pin "8") (pinfunction "8_8") (pintype "passive"))
      (node (ref "JP5") (pin "6") (pinfunction "6_6") (pintype "passive"))
      (node (ref "U$2") (pin "5") (pinfunction "O_5") (pintype "output"))
    )
    (net (code "97") (name "Net-(IC9D-OUT)") (class "Default")
      (node (ref "IC9") (pin "14") (pinfunction "OUT_14") (pintype "output"))
      (node (ref "JP15") (pin "10") (pinfunction "10_10") (pintype "passive"))
      (node (ref "JP5") (pin "8") (pinfunction "8_8") (pintype "passive"))
      (node (ref "U$3") (pin "7") (pinfunction "O_7") (pintype "output"))
    )
    (net (code "98") (name "Net-(J1-Pad4)") (class "Default")
      (node (ref "J1") (pin "4") (pinfunction "4_4") (pintype "passive"))
      (node (ref "J2") (pin "4") (pinfunction "4_4") (pintype "passive"))
    )
    (net (code "99") (name "Net-(J1-Pad5)") (class "Default")
      (node (ref "J1") (pin "5") (pinfunction "5_5") (pintype "passive"))
      (node (ref "J2") (pin "5") (pinfunction "5_5") (pintype "passive"))
    )
    (net (code "100") (name "Net-(J1-Pad8)") (class "Default")
      (node (ref "J1") (pin "8") (pinfunction "8_8") (pintype "passive"))
      (node (ref "J2") (pin "8") (pinfunction "8_8") (pintype "passive"))
      (node (ref "R40") (pin "1") (pinfunction "1_1") (pintype "passive"))
    )
    (net (code "101") (name "Net-(JP4-Pad3)") (class "Default")
      (node (ref "JP4") (pin "3") (pinfunction "3_3") (pintype "passive"))
      (node (ref "R40") (pin "2") (pinfunction "2_2") (pintype "passive"))
    )
    (net (code "102") (name "Net-(JP13-Pad1)") (class "Default")
      (node (ref "JP13") (pin "1") (pinfunction "1_1") (pintype "passive"))
      (node (ref "JP3") (pin "1") (pinfunction "1_1") (pintype "passive"))
      (node (ref "R44") (pin "2") (pinfunction "2_2") (pintype "passive"))
      (node (ref "R53") (pin "2") (pinfunction "2_2") (pintype "passive"))
      (node (ref "RN4") (pin "1") (pinfunction "1_1") (pintype "passive"))
      (node (ref "RN5") (pin "9") (pinfunction "9_9") (pintype "passive"))
    )
    (net (code "103") (name "Net-(JP14-Pad1)") (class "Default")
      (node (ref "JP14") (pin "1") (pinfunction "1_1") (pintype "passive"))
      (node (ref "JP2") (pin "1") (pinfunction "1_1") (pintype "passive"))
      (node (ref "R35") (pin "2") (pinfunction "2_2") (pintype "passive"))
      (node (ref "R45") (pin "2") (pinfunction "2_2") (pintype "passive"))
      (node (ref "RN1") (pin "1") (pinfunction "1_1") (pintype "passive"))
      (node (ref "RN2") (pin "9") (pinfunction "9_9") (pintype "passive"))
    )
    (net (code "104") (name "Net-(Q1-G)") (class "Default")
      (node (ref "Q1") (pin "1") (pinfunction "G_1") (pintype "passive"))
      (node (ref "R3") (pin "2") (pinfunction "2_2") (pintype "passive"))
    )
    (net (code "105") (name "Net-(Q2-G)") (class "Default")
      (node (ref "Q2") (pin "1") (pinfunction "G_1") (pintype "passive"))
      (node (ref "R4") (pin "2") (pinfunction "2_2") (pintype "passive"))
    )
    (net (code "106") (name "Net-(Q3-G)") (class "Default")
      (node (ref "Q3") (pin "1") (pinfunction "G_1") (pintype "passive"))
      (node (ref "R5") (pin "2") (pinfunction "2_2") (pintype "passive"))
    )
    (net (code "107") (name "Net-(Q4-G)") (class "Default")
      (node (ref "Q4") (pin "1") (pinfunction "G_1") (pintype "passive"))
      (node (ref "R6") (pin "2") (pinfunction "2_2") (pintype "passive"))
    )
    (net (code "108") (name "Net-(Q5-G)") (class "Default")
      (node (ref "Q5") (pin "1") (pinfunction "G_1") (pintype "passive"))
      (node (ref "R7") (pin "2") (pinfunction "2_2") (pintype "passive"))
    )
    (net (code "109") (name "Net-(Q6-G)") (class "Default")
      (node (ref "Q6") (pin "1") (pinfunction "G_1") (pintype "passive"))
      (node (ref "R8") (pin "2") (pinfunction "2_2") (pintype "passive"))
    )
    (net (code "110") (name "Net-(Q7-G)") (class "Default")
      (node (ref "Q7") (pin "1") (pinfunction "G_1") (pintype "passive"))
      (node (ref "R9") (pin "2") (pinfunction "2_2") (pintype "passive"))
    )
    (net (code "111") (name "Net-(Q8-G)") (class "Default")
      (node (ref "Q8") (pin "1") (pinfunction "G_1") (pintype "passive"))
      (node (ref "R10") (pin "2") (pinfunction "2_2") (pintype "passive"))
    )
    (net (code "112") (name "Net-(Q9-G)") (class "Default")
      (node (ref "Q9") (pin "1") (pinfunction "G_1") (pintype "passive"))
      (node (ref "R11") (pin "2") (pinfunction "2_2") (pintype "passive"))
    )
    (net (code "113") (name "Net-(Q10-G)") (class "Default")
      (node (ref "Q10") (pin "1") (pinfunction "G_1") (pintype "passive"))
      (node (ref "R12") (pin "2") (pinfunction "2_2") (pintype "passive"))
    )
    (net (code "114") (name "Net-(Q11-G)") (class "Default")
      (node (ref "Q11") (pin "1") (pinfunction "G_1") (pintype "passive"))
      (node (ref "R13") (pin "2") (pinfunction "2_2") (pintype "passive"))
    )
    (net (code "115") (name "Net-(Q12-G)") (class "Default")
      (node (ref "Q12") (pin "1") (pinfunction "G_1") (pintype "passive"))
      (node (ref "R14") (pin "2") (pinfunction "2_2") (pintype "passive"))
    )
    (net (code "116") (name "Net-(Q13-G)") (class "Default")
      (node (ref "Q13") (pin "1") (pinfunction "G_1") (pintype "passive"))
      (node (ref "R15") (pin "2") (pinfunction "2_2") (pintype "passive"))
    )
    (net (code "117") (name "Net-(Q14-G)") (class "Default")
      (node (ref "Q14") (pin "1") (pinfunction "G_1") (pintype "passive"))
      (node (ref "R16") (pin "2") (pinfunction "2_2") (pintype "passive"))
    )
    (net (code "118") (name "Net-(Q15-G)") (class "Default")
      (node (ref "Q15") (pin "1") (pinfunction "G_1") (pintype "passive"))
      (node (ref "R17") (pin "2") (pinfunction "2_2") (pintype "passive"))
    )
    (net (code "119") (name "Net-(Q16-G)") (class "Default")
      (node (ref "Q16") (pin "1") (pinfunction "G_1") (pintype "passive"))
      (node (ref "R18") (pin "2") (pinfunction "2_2") (pintype "passive"))
    )
    (net (code "120") (name "Net-(RN1B-1)") (class "Default")
      (node (ref "JP14") (pin "2") (pinfunction "2_2") (pintype "passive"))
      (node (ref "JP2") (pin "2") (pinfunction "2_2") (pintype "passive"))
      (node (ref "R34") (pin "2") (pinfunction "2_2") (pintype "passive"))
      (node (ref "R46") (pin "1") (pinfunction "1_1") (pintype "passive"))
      (node (ref "RN1") (pin "2") (pinfunction "1_2") (pintype "passive"))
      (node (ref "RN2") (pin "8") (pinfunction "8_8") (pintype "passive"))
    )
    (net (code "121") (name "Net-(RN1C-1)") (class "Default")
      (node (ref "JP14") (pin "3") (pinfunction "3_3") (pintype "passive"))
      (node (ref "JP2") (pin "3") (pinfunction "3_3") (pintype "passive"))
      (node (ref "R33") (pin "2") (pinfunction "2_2") (pintype "passive"))
      (node (ref "R47") (pin "1") (pinfunction "1_1") (pintype "passive"))
      (node (ref "RN1") (pin "3") (pinfunction "1_3") (pintype "passive"))
      (node (ref "RN2") (pin "7") (pinfunction "7_7") (pintype "passive"))
    )
    (net (code "122") (name "Net-(RN1D-1)") (class "Default")
      (node (ref "JP14") (pin "4") (pinfunction "4_4") (pintype "passive"))
      (node (ref "JP2") (pin "4") (pinfunction "4_4") (pintype "passive"))
      (node (ref "R32") (pin "2") (pinfunction "2_2") (pintype "passive"))
      (node (ref "R48") (pin "1") (pinfunction "1_1") (pintype "passive"))
      (node (ref "RN1") (pin "4") (pinfunction "1_4") (pintype "passive"))
      (node (ref "RN2") (pin "6") (pinfunction "6_6") (pintype "passive"))
    )
    (net (code "123") (name "Net-(RN1E-1)") (class "Default")
      (node (ref "JP14") (pin "7") (pinfunction "7_7") (pintype "passive"))
      (node (ref "JP2") (pin "5") (pinfunction "5_5") (pintype "passive"))
      (node (ref "R31") (pin "2") (pinfunction "2_2") (pintype "passive"))
      (node (ref "R49") (pin "1") (pinfunction "1_1") (pintype "passive"))
      (node (ref "RN1") (pin "5") (pinfunction "1_5") (pintype "passive"))
      (node (ref "RN2") (pin "5") (pinfunction "5_5") (pintype "passive"))
    )
    (net (code "124") (name "Net-(RN1F-1)") (class "Default")
      (node (ref "JP14") (pin "8") (pinfunction "8_8") (pintype "passive"))
      (node (ref "JP2") (pin "6") (pinfunction "6_6") (pintype "passive"))
      (node (ref "R30") (pin "2") (pinfunction "2_2") (pintype "passive"))
      (node (ref "R50") (pin "1") (pinfunction "1_1") (pintype "passive"))
      (node (ref "RN1") (pin "6") (pinfunction "1_6") (pintype "passive"))
      (node (ref "RN2") (pin "4") (pinfunction "4_4") (pintype "passive"))
    )
    (net (code "125") (name "Net-(RN1G-1)") (class "Default")
      (node (ref "JP14") (pin "9") (pinfunction "9_9") (pintype "passive"))
      (node (ref "JP2") (pin "7") (pinfunction "7_7") (pintype "passive"))
      (node (ref "R29") (pin "2") (pinfunction "2_2") (pintype "passive"))
      (node (ref "R51") (pin "1") (pinfunction "1_1") (pintype "passive"))
      (node (ref "RN1") (pin "7") (pinfunction "1_7") (pintype "passive"))
      (node (ref "RN2") (pin "3") (pinfunction "3_3") (pintype "passive"))
    )
    (net (code "126") (name "Net-(RN1H-1)") (class "Default")
      (node (ref "JP14") (pin "10") (pinfunction "10_10") (pintype "passive"))
      (node (ref "JP2") (pin "8") (pinfunction "8_8") (pintype "passive"))
      (node (ref "R28") (pin "2") (pinfunction "2_2") (pintype "passive"))
      (node (ref "R52") (pin "1") (pinfunction "1_1") (pintype "passive"))
      (node (ref "RN1") (pin "8") (pinfunction "1_8") (pintype "passive"))
      (node (ref "RN2") (pin "2") (pinfunction "2_2") (pintype "passive"))
    )
    (net (code "127") (name "Net-(RN4B-1)") (class "Default")
      (node (ref "JP13") (pin "2") (pinfunction "2_2") (pintype "passive"))
      (node (ref "JP3") (pin "2") (pinfunction "2_2") (pintype "passive"))
      (node (ref "R43") (pin "2") (pinfunction "2_2") (pintype "passive"))
      (node (ref "R54") (pin "2") (pinfunction "2_2") (pintype "passive"))
      (node (ref "RN4") (pin "2") (pinfunction "1_2") (pintype "passive"))
      (node (ref "RN5") (pin "8") (pinfunction "8_8") (pintype "passive"))
    )
    (net (code "128") (name "Net-(RN4C-1)") (class "Default")
      (node (ref "JP13") (pin "3") (pinfunction "3_3") (pintype "passive"))
      (node (ref "JP3") (pin "3") (pinfunction "3_3") (pintype "passive"))
      (node (ref "R42") (pin "2") (pinfunction "2_2") (pintype "passive"))
      (node (ref "R55") (pin "2") (pinfunction "2_2") (pintype "passive"))
      (node (ref "RN4") (pin "3") (pinfunction "1_3") (pintype "passive"))
      (node (ref "RN5") (pin "7") (pinfunction "7_7") (pintype "passive"))
    )
    (net (code "129") (name "Net-(RN4D-1)") (class "Default")
      (node (ref "JP13") (pin "4") (pinfunction "4_4") (pintype "passive"))
      (node (ref "JP3") (pin "4") (pinfunction "4_4") (pintype "passive"))
      (node (ref "R41") (pin "2") (pinfunction "2_2") (pintype "passive"))
      (node (ref "R56") (pin "2") (pinfunction "2_2") (pintype "passive"))
      (node (ref "RN4") (pin "4") (pinfunction "1_4") (pintype "passive"))
      (node (ref "RN5") (pin "6") (pinfunction "6_6") (pintype "passive"))
    )
    (net (code "130") (name "Net-(RN4E-1)") (class "Default")
      (node (ref "JP13") (pin "7") (pinfunction "7_7") (pintype "passive"))
      (node (ref "JP3") (pin "5") (pinfunction "5_5") (pintype "passive"))
      (node (ref "R39") (pin "2") (pinfunction "2_2") (pintype "passive"))
      (node (ref "R57") (pin "2") (pinfunction "2_2") (pintype "passive"))
      (node (ref "RN4") (pin "5") (pinfunction "1_5") (pintype "passive"))
      (node (ref "RN5") (pin "5") (pinfunction "5_5") (pintype "passive"))
    )
    (net (code "131") (name "Net-(RN4F-1)") (class "Default")
      (node (ref "JP13") (pin "8") (pinfunction "8_8") (pintype "passive"))
      (node (ref "JP3") (pin "6") (pinfunction "6_6") (pintype "passive"))
      (node (ref "R38") (pin "2") (pinfunction "2_2") (pintype "passive"))
      (node (ref "R58") (pin "2") (pinfunction "2_2") (pintype "passive"))
      (node (ref "RN4") (pin "6") (pinfunction "1_6") (pintype "passive"))
      (node (ref "RN5") (pin "4") (pinfunction "4_4") (pintype "passive"))
    )
    (net (code "132") (name "Net-(RN4G-1)") (class "Default")
      (node (ref "JP13") (pin "9") (pinfunction "9_9") (pintype "passive"))
      (node (ref "JP3") (pin "7") (pinfunction "7_7") (pintype "passive"))
      (node (ref "R37") (pin "2") (pinfunction "2_2") (pintype "passive"))
      (node (ref "R59") (pin "2") (pinfunction "2_2") (pintype "passive"))
      (node (ref "RN4") (pin "7") (pinfunction "1_7") (pintype "passive"))
      (node (ref "RN5") (pin "3") (pinfunction "3_3") (pintype "passive"))
    )
    (net (code "133") (name "Net-(RN4H-1)") (class "Default")
      (node (ref "JP13") (pin "10") (pinfunction "10_10") (pintype "passive"))
      (node (ref "JP3") (pin "8") (pinfunction "8_8") (pintype "passive"))
      (node (ref "R36") (pin "2") (pinfunction "2_2") (pintype "passive"))
      (node (ref "R60") (pin "2") (pinfunction "2_2") (pintype "passive"))
      (node (ref "RN4") (pin "8") (pinfunction "1_8") (pintype "passive"))
      (node (ref "RN5") (pin "2") (pinfunction "2_2") (pintype "passive"))
    )
    (net (code "134") (name "Net-(SJ13-1)") (class "Default")
      (node (ref "SJ13") (pin "P$1") (pinfunction "1_P$1") (pintype "passive"))
      (node (ref "U$1") (pin "PB14") (pinfunction "PB14_PB14") (pintype "bidirectional"))
    )
    (net (code "135") (name "Net-(SJ14-1)") (class "Default")
      (node (ref "SJ14") (pin "P$1") (pinfunction "1_P$1") (pintype "passive"))
      (node (ref "U$1") (pin "VIN2") (pinfunction "VIN2_VIN2") (pintype "power_in"))
    )
    (net (code "136") (name "Net-(SJ16-2)") (class "Default")
      (node (ref "JP9") (pin "2") (pinfunction "2_2") (pintype "passive"))
      (node (ref "SJ15") (pin "2") (pinfunction "2_2") (pintype "passive"))
      (node (ref "SJ16") (pin "P$2") (pinfunction "2_P$2") (pintype "passive"))
    )
    (net (code "137") (name "OLAT") (class "Default")
      (node (ref "IC3") (pin "12") (pinfunction "RCK_12") (pintype "input"))
      (node (ref "IC5") (pin "12") (pinfunction "RCK_12") (pintype "input"))
      (node (ref "R21") (pin "1") (pinfunction "1_1") (pintype "passive"))
      (node (ref "U$1") (pin "PA8") (pinfunction "PA8_PA8") (pintype "bidirectional"))
    )
    (net (code "138") (name "SCK") (class "Default")
      (node (ref "IC3") (pin "11") (pinfunction "SCK_11") (pintype "input"))
      (node (ref "IC5") (pin "11") (pinfunction "SCK_11") (pintype "input"))
      (node (ref "JP9") (pin "3") (pinfunction "3_3") (pintype "passive"))
      (node (ref "R19") (pin "1") (pinfunction "1_1") (pintype "passive"))
      (node (ref "U$1") (pin "PB3") (pinfunction "PB3_PB3") (pintype "bidirectional"))
    )
    (net (code "139") (name "SCK2") (class "Default")
      (node (ref "IC1") (pin "7") (pinfunction "CLK_7") (pintype "input"))
      (node (ref "IC4") (pin "7") (pinfunction "CLK_7") (pintype "input"))
      (node (ref "U$1") (pin "PB10") (pinfunction "PB10_PB10") (pintype "bidirectional"))
    )
    (net (code "140") (name "SLNK1") (class "Default")
      (node (ref "IC3") (pin "14") (pinfunction "SER_14") (pintype "input"))
      (node (ref "IC5") (pin "9") (pinfunction "QH*_9") (pintype "tri_state"))
      (node (ref "SJ17") (pin "P$1") (pinfunction "1_P$1") (pintype "passive"))
    )
    (net (code "141") (name "SLNK2") (class "Default")
      (node (ref "IC3") (pin "9") (pinfunction "QH*_9") (pintype "tri_state"))
      (node (ref "SJ16") (pin "P$1") (pinfunction "1_P$1") (pintype "passive"))
    )
    (net (code "142") (name "SLNK3") (class "Default")
      (node (ref "IC1") (pin "13") (pinfunction "QH_13") (pintype "output"))
      (node (ref "IC4") (pin "1") (pinfunction "SER_1") (pintype "input"))
    )
    (net (code "143") (name "SRV1") (class "Default")
      (node (ref "JP7") (pin "2") (pinfunction "2_2") (pintype "passive"))
      (node (ref "R25") (pin "2") (pinfunction "2_2") (pintype "passive"))
      (node (ref "U$1") (pin "PC9") (pinfunction "PC9_PC9") (pintype "bidirectional"))
    )
    (net (code "144") (name "SRV2") (class "Default")
      (node (ref "JP7") (pin "1") (pinfunction "1_1") (pintype "passive"))
      (node (ref "R24") (pin "2") (pinfunction "2_2") (pintype "passive"))
      (node (ref "U$1") (pin "PC7") (pinfunction "PC7_PC7") (pintype "bidirectional"))
    )
    (net (code "145") (name "SRV3") (class "Default")
      (node (ref "JP11") (pin "2") (pinfunction "2_2") (pintype "passive"))
      (node (ref "R26") (pin "2") (pinfunction "2_2") (pintype "passive"))
      (node (ref "U$1") (pin "PC8") (pinfunction "PC8_PC8") (pintype "bidirectional"))
    )
    (net (code "146") (name "SRV4") (class "Default")
      (node (ref "JP11") (pin "1") (pinfunction "1_1") (pintype "passive"))
      (node (ref "R27") (pin "2") (pinfunction "2_2") (pintype "passive"))
      (node (ref "U$1") (pin "PC6") (pinfunction "PC6_PC6") (pintype "bidirectional"))
    )
    (net (code "147") (name "TIN3") (class "Default")
      (node (ref "IC9") (pin "10") (pinfunction "+IN_10") (pintype "input"))
      (node (ref "U$1") (pin "PB15") (pinfunction "PB15_PB15") (pintype "bidirectional"))
      (node (ref "U$2") (pin "4") (pinfunction "I_4") (pintype "input"))
    )
    (net (code "148") (name "TIN4") (class "Default")
      (node (ref "IC9") (pin "12") (pinfunction "+IN_12") (pintype "input"))
      (node (ref "U$1") (pin "PB12") (pinfunction "PB12_PB12") (pintype "bidirectional"))
      (node (ref "U$3") (pin "2") (pinfunction "I_2") (pintype "input"))
    )
    (net (code "149") (name "V+") (class "Default")
      (node (ref "AP1509") (pin "3") (pinfunction "FB_3") (pintype "bidirectional"))
      (node (ref "C1") (pin "1") (pinfunction "1_1") (pintype "passive"))
      (node (ref "C2") (pin "+") (pinfunction "+_+") (pintype "passive"))
      (node (ref "IC10") (pin "1") (pinfunction "FB_1") (pintype "input"))
      (node (ref "L1") (pin "1") (pinfunction "1_1") (pintype "passive"))
      (node (ref "U$1") (pin "E5V") (pinfunction "E5V_E5V") (pintype "power_in"))
    )
    (net (code "150") (name "unconnected-(H1-MOUNT-PadB3,3)") (class "Default")
      (node (ref "H1") (pin "B3,3") (pinfunction "MOUNT_B3,3") (pintype "passive"))
    )
    (net (code "151") (name "unconnected-(H2-MOUNT-PadB3,3)") (class "Default")
      (node (ref "H2") (pin "B3,3") (pinfunction "MOUNT_B3,3") (pintype "passive"))
    )
    (net (code "152") (name "unconnected-(H3-MOUNT-PadB3,3)") (class "Default")
      (node (ref "H3") (pin "B3,3") (pinfunction "MOUNT_B3,3") (pintype "passive"))
    )
    (net (code "153") (name "unconnected-(H4-MOUNT-PadB3,3)") (class "Default")
      (node (ref "H4") (pin "B3,3") (pinfunction "MOUNT_B3,3") (pintype "passive"))
    )
    (net (code "154") (name "unconnected-(J3-Pad2)") (class "Default")
      (node (ref "J3") (pin "2") (pinfunction "2_2") (pintype "passive"))
    )
    (net (code "155") (name "unconnected-(U$1-PadBOOT0)") (class "Default")
      (node (ref "U$1") (pin "BOOT0") (pinfunction "BOOT0_BOOT0") (pintype "bidirectional"))
    )
    (net (code "156") (name "unconnected-(U$1-PadIOREF2)") (class "Default")
      (node (ref "U$1") (pin "IOREF2") (pinfunction "IOREF2_IOREF2") (pintype "input"))
    )
    (net (code "157") (name "unconnected-(U$1-PadNC1-PF7)") (class "Default")
      (node (ref "U$1") (pin "NC1-PF7") (pinfunction "NC1-PF7_NC1-PF7") (pintype "bidirectional"))
    )
    (net (code "158") (name "unconnected-(U$1-PadNC2-PF6)") (class "Default")
      (node (ref "U$1") (pin "NC2-PF6") (pinfunction "NC2-PF6_NC2-PF6") (pintype "bidirectional"))
    )
    (net (code "159") (name "unconnected-(U$1-PadNC3)") (class "Default")
      (node (ref "U$1") (pin "NC3") (pinfunction "NC3_NC3") (pintype "no_connect"))
    )
    (net (code "160") (name "unconnected-(U$1-PadNC4)") (class "Default")
      (node (ref "U$1") (pin "NC4") (pinfunction "NC4_NC4") (pintype "no_connect"))
    )
    (net (code "161") (name "unconnected-(U$1-PadNC5-PD8)") (class "Default")
      (node (ref "U$1") (pin "NC5-PD8") (pinfunction "NC5-PD8_NC5-PD8") (pintype "bidirectional"))
    )
    (net (code "162") (name "unconnected-(U$1-PadNC6-PB11)") (class "Default")
      (node (ref "U$1") (pin "NC6-PB11") (pinfunction "NC6-PB11_NC6-PB11") (pintype "no_connect"))
    )
    (net (code "163") (name "unconnected-(U$1-PadNC7-PF5)") (class "Default")
      (node (ref "U$1") (pin "NC7-PF5") (pinfunction "NC7-PF5_NC7-PF5") (pintype "bidirectional"))
    )
    (net (code "164") (name "unconnected-(U$1-PadNC8-PF4)") (class "Default")
      (node (ref "U$1") (pin "NC8-PF4") (pinfunction "NC8-PF4_NC8-PF4") (pintype "bidirectional"))
    )
    (net (code "165") (name "unconnected-(U$1-PadNRESET)") (class "Default")
      (node (ref "U$1") (pin "NRESET") (pinfunction "NRESET_NRESET") (pintype "input"))
    )
    (net (code "166") (name "unconnected-(U$1-PadPA1)") (class "Default")
      (node (ref "U$1") (pin "PA1") (pinfunction "PA1_PA1") (pintype "bidirectional"))
    )
    (net (code "167") (name "unconnected-(U$1-PadPA2)") (class "Default")
      (node (ref "U$1") (pin "PA2") (pinfunction "PA2_PA2") (pintype "bidirectional"))
    )
    (net (code "168") (name "unconnected-(U$1-PadPA3)") (class "Default")
      (node (ref "U$1") (pin "PA3") (pinfunction "PA3_PA3") (pintype "bidirectional"))
    )
    (net (code "169") (name "unconnected-(U$1-PadPA5)") (class "Default")
      (node (ref "U$1") (pin "PA5") (pinfunction "PA5_PA5") (pintype "bidirectional"))
    )
    (net (code "170") (name "unconnected-(U$1-PadPA7)") (class "Default")
      (node (ref "U$1") (pin "PA7") (pinfunction "PA7_PA7") (pintype "bidirectional"))
    )
    (net (code "171") (name "unconnected-(U$1-PadPA9)") (class "Default")
      (node (ref "U$1") (pin "PA9") (pinfunction "PA9_PA9") (pintype "bidirectional"))
    )
    (net (code "172") (name "unconnected-(U$1-PadPA10)") (class "Default")
      (node (ref "U$1") (pin "PA10") (pinfunction "PA10_PA10") (pintype "bidirectional"))
    )
    (net (code "173") (name "unconnected-(U$1-PadPA11)") (class "Default")
      (node (ref "U$1") (pin "PA11") (pinfunction "PA11_PA11") (pintype "bidirectional"))
    )
    (net (code "174") (name "unconnected-(U$1-PadPA12)") (class "Default")
      (node (ref "U$1") (pin "PA12") (pinfunction "PA12_PA12") (pintype "bidirectional"))
    )
    (net (code "175") (name "unconnected-(U$1-PadPA13)") (class "Default")
      (node (ref "U$1") (pin "PA13") (pinfunction "PA13_PA13") (pintype "bidirectional"))
    )
    (net (code "176") (name "unconnected-(U$1-PadPA14)") (class "Default")
      (node (ref "U$1") (pin "PA14") (pinfunction "PA14_PA14") (pintype "bidirectional"))
    )
    (net (code "177") (name "unconnected-(U$1-PadPB0)") (class "Default")
      (node (ref "U$1") (pin "PB0") (pinfunction "PB0_PB0") (pintype "bidirectional"))
    )
    (net (code "178") (name "unconnected-(U$1-PadPB13)") (class "Default")
      (node (ref "U$1") (pin "PB13") (pinfunction "PB13_PB13") (pintype "bidirectional"))
    )
    (net (code "179") (name "unconnected-(U$1-PadPC1)") (class "Default")
      (node (ref "U$1") (pin "PC1") (pinfunction "PC1_PC1") (pintype "bidirectional"))
    )
    (net (code "180") (name "unconnected-(U$1-PadPC4)") (class "Default")
      (node (ref "U$1") (pin "PC4") (pinfunction "PC4_PC4") (pintype "bidirectional"))
    )
    (net (code "181") (name "unconnected-(U$1-PadPC5)") (class "Default")
      (node (ref "U$1") (pin "PC5") (pinfunction "PC5_PC5") (pintype "bidirectional"))
    )
    (net (code "182") (name "unconnected-(U$1-PadPC13)") (class "Default")
      (node (ref "U$1") (pin "PC13") (pinfunction "PC13_PC13") (pintype "bidirectional"))
    )
    (net (code "183") (name "unconnected-(U$1-PadPC14)") (class "Default")
      (node (ref "U$1") (pin "PC14") (pinfunction "PC14_PC14") (pintype "bidirectional"))
    )
    (net (code "184") (name "unconnected-(U$1-PadPC15)") (class "Default")
      (node (ref "U$1") (pin "PC15") (pinfunction "PC15_PC15") (pintype "bidirectional"))
    )
    (net (code "185") (name "unconnected-(U$1-PadPF0-PH0)") (class "Default")
      (node (ref "U$1") (pin "PF0-PH0") (pinfunction "PF0-PH0_PF0-PH0") (pintype "bidirectional"))
    )
  )
)
